# lighthouse-booster.net
KiCad netlist of a schematic drawn in EAGLE
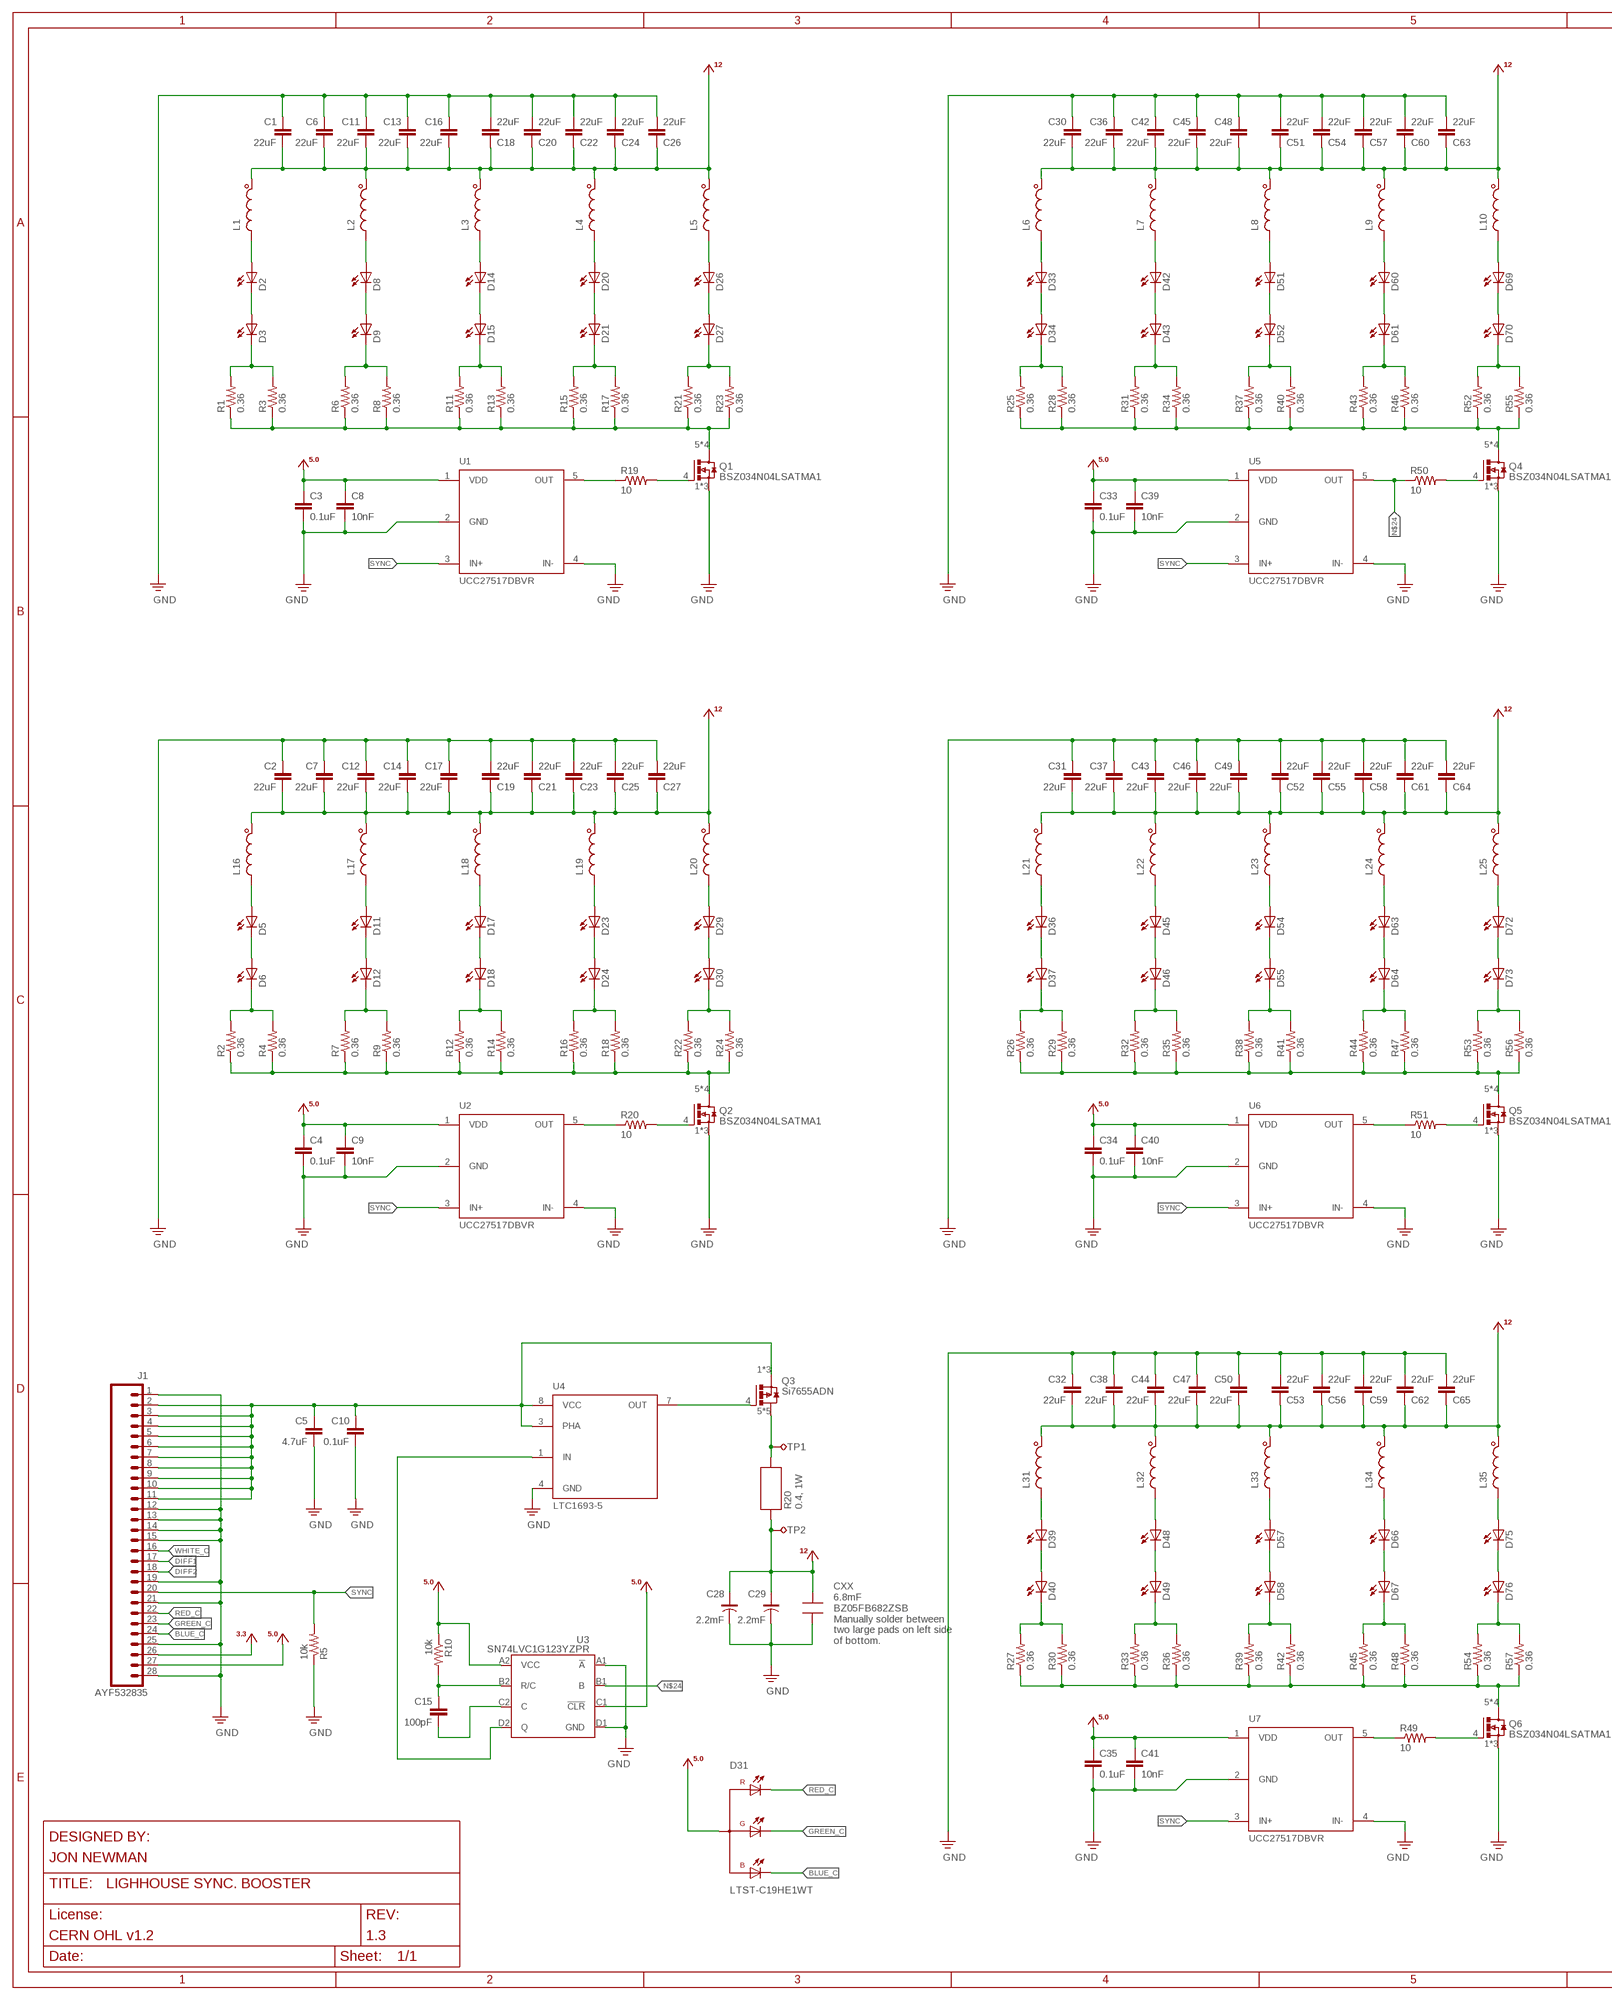
[diagram p0: schematic, sheet 1, part 1 of 2]
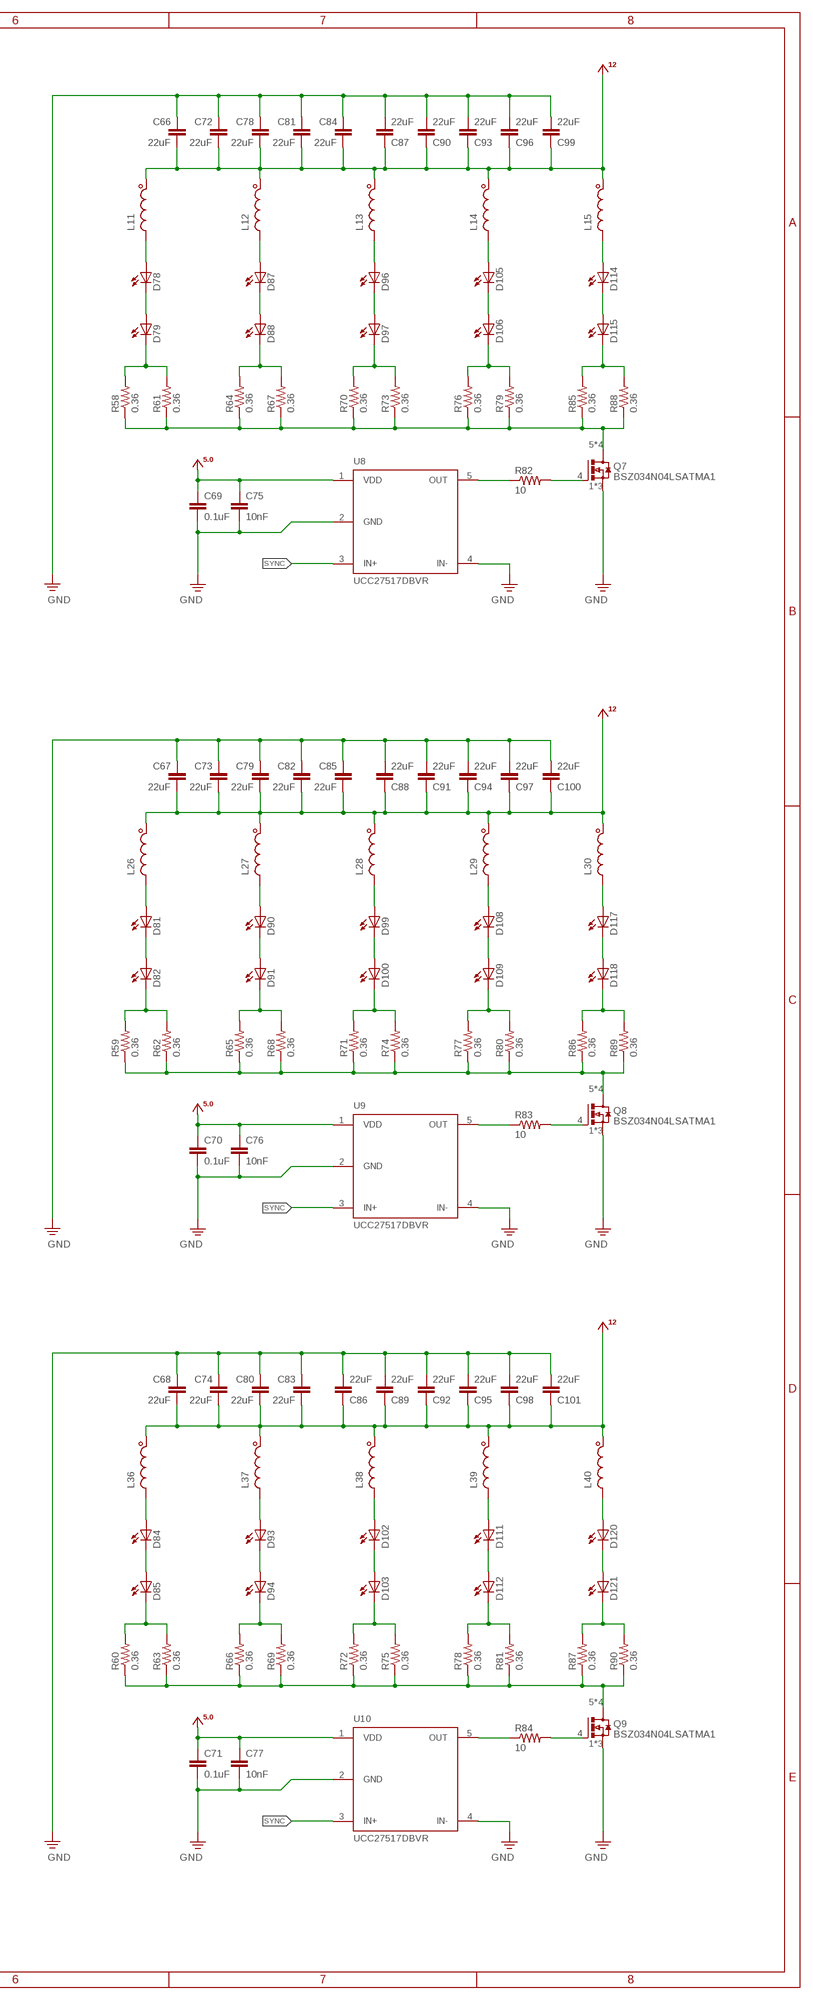
[diagram p1: schematic, sheet 1, part 2 of 2]

(export (version "E")
  (design (tool "Eeschema 10.0.6"))
  (components
    (comp (ref "C1")
      (value "22uF")
      (footprint "eagle-import:0805T")
      (libsource (lib "eagle-import") (part "C_0805T"))
    )
    (comp (ref "C2")
      (value "22uF")
      (footprint "eagle-import:0805T")
      (libsource (lib "eagle-import") (part "C_0805T"))
    )
    (comp (ref "C3")
      (value "0.1uF")
      (footprint "eagle-import:0402T")
      (libsource (lib "eagle-import") (part "C_0402T"))
    )
    (comp (ref "C4")
      (value "0.1uF")
      (footprint "eagle-import:0402T")
      (libsource (lib "eagle-import") (part "C_0402T"))
    )
    (comp (ref "C5")
      (value "4.7uF")
      (footprint "eagle-import:0603T")
      (libsource (lib "eagle-import") (part "C_0603T"))
    )
    (comp (ref "C6")
      (value "22uF")
      (footprint "eagle-import:0805T")
      (libsource (lib "eagle-import") (part "C_0805T"))
    )
    (comp (ref "C7")
      (value "22uF")
      (footprint "eagle-import:0805T")
      (libsource (lib "eagle-import") (part "C_0805T"))
    )
    (comp (ref "C8")
      (value "10nF")
      (footprint "eagle-import:0402T")
      (libsource (lib "eagle-import") (part "C_0402T"))
    )
    (comp (ref "C9")
      (value "10nF")
      (footprint "eagle-import:0402T")
      (libsource (lib "eagle-import") (part "C_0402T"))
    )
    (comp (ref "C10")
      (value "0.1uF")
      (footprint "eagle-import:0402T")
      (libsource (lib "eagle-import") (part "C_0402T"))
    )
    (comp (ref "C11")
      (value "22uF")
      (footprint "eagle-import:0805T")
      (libsource (lib "eagle-import") (part "C_0805T"))
    )
    (comp (ref "C12")
      (value "22uF")
      (footprint "eagle-import:0805T")
      (libsource (lib "eagle-import") (part "C_0805T"))
    )
    (comp (ref "C13")
      (value "22uF")
      (footprint "eagle-import:0805T")
      (libsource (lib "eagle-import") (part "C_0805T"))
    )
    (comp (ref "C14")
      (value "22uF")
      (footprint "eagle-import:0805T")
      (libsource (lib "eagle-import") (part "C_0805T"))
    )
    (comp (ref "C15")
      (value "100pF")
      (footprint "eagle-import:0402T")
      (libsource (lib "eagle-import") (part "C_0402T"))
    )
    (comp (ref "C16")
      (value "22uF")
      (footprint "eagle-import:0805T")
      (libsource (lib "eagle-import") (part "C_0805T"))
    )
    (comp (ref "C17")
      (value "22uF")
      (footprint "eagle-import:0805T")
      (libsource (lib "eagle-import") (part "C_0805T"))
    )
    (comp (ref "C18")
      (value "22uF")
      (footprint "eagle-import:0805T")
      (libsource (lib "eagle-import") (part "C_0805T"))
    )
    (comp (ref "C19")
      (value "22uF")
      (footprint "eagle-import:0805T")
      (libsource (lib "eagle-import") (part "C_0805T"))
    )
    (comp (ref "C20")
      (value "22uF")
      (footprint "eagle-import:0805T")
      (libsource (lib "eagle-import") (part "C_0805T"))
    )
    (comp (ref "C21")
      (value "22uF")
      (footprint "eagle-import:0805T")
      (libsource (lib "eagle-import") (part "C_0805T"))
    )
    (comp (ref "C22")
      (value "22uF")
      (footprint "eagle-import:0805T")
      (libsource (lib "eagle-import") (part "C_0805T"))
    )
    (comp (ref "C23")
      (value "22uF")
      (footprint "eagle-import:0805T")
      (libsource (lib "eagle-import") (part "C_0805T"))
    )
    (comp (ref "C24")
      (value "22uF")
      (footprint "eagle-import:0805T")
      (libsource (lib "eagle-import") (part "C_0805T"))
    )
    (comp (ref "C25")
      (value "22uF")
      (footprint "eagle-import:0805T")
      (libsource (lib "eagle-import") (part "C_0805T"))
    )
    (comp (ref "C26")
      (value "22uF")
      (footprint "eagle-import:0805T")
      (libsource (lib "eagle-import") (part "C_0805T"))
    )
    (comp (ref "C27")
      (value "22uF")
      (footprint "eagle-import:0805T")
      (libsource (lib "eagle-import") (part "C_0805T"))
    )
    (comp (ref "C28")
      (value "2.2mF")
      (footprint "eagle-import:C5MMA-SMD")
      (libsource (lib "eagle-import") (part "C-POL_C5MMA-SMD"))
    )
    (comp (ref "C29")
      (value "2.2mF")
      (footprint "eagle-import:C5MMA-SMD")
      (libsource (lib "eagle-import") (part "C-POL_C5MMA-SMD"))
    )
    (comp (ref "C30")
      (value "22uF")
      (footprint "eagle-import:0805T")
      (libsource (lib "eagle-import") (part "C_0805T"))
    )
    (comp (ref "C31")
      (value "22uF")
      (footprint "eagle-import:0805T")
      (libsource (lib "eagle-import") (part "C_0805T"))
    )
    (comp (ref "C32")
      (value "22uF")
      (footprint "eagle-import:0805T")
      (libsource (lib "eagle-import") (part "C_0805T"))
    )
    (comp (ref "C33")
      (value "0.1uF")
      (footprint "eagle-import:0402T")
      (libsource (lib "eagle-import") (part "C_0402T"))
    )
    (comp (ref "C34")
      (value "0.1uF")
      (footprint "eagle-import:0402T")
      (libsource (lib "eagle-import") (part "C_0402T"))
    )
    (comp (ref "C35")
      (value "0.1uF")
      (footprint "eagle-import:0402T")
      (libsource (lib "eagle-import") (part "C_0402T"))
    )
    (comp (ref "C36")
      (value "22uF")
      (footprint "eagle-import:0805T")
      (libsource (lib "eagle-import") (part "C_0805T"))
    )
    (comp (ref "C37")
      (value "22uF")
      (footprint "eagle-import:0805T")
      (libsource (lib "eagle-import") (part "C_0805T"))
    )
    (comp (ref "C38")
      (value "22uF")
      (footprint "eagle-import:0805T")
      (libsource (lib "eagle-import") (part "C_0805T"))
    )
    (comp (ref "C39")
      (value "10nF")
      (footprint "eagle-import:0402T")
      (libsource (lib "eagle-import") (part "C_0402T"))
    )
    (comp (ref "C40")
      (value "10nF")
      (footprint "eagle-import:0402T")
      (libsource (lib "eagle-import") (part "C_0402T"))
    )
    (comp (ref "C41")
      (value "10nF")
      (footprint "eagle-import:0402T")
      (libsource (lib "eagle-import") (part "C_0402T"))
    )
    (comp (ref "C42")
      (value "22uF")
      (footprint "eagle-import:0805T")
      (libsource (lib "eagle-import") (part "C_0805T"))
    )
    (comp (ref "C43")
      (value "22uF")
      (footprint "eagle-import:0805T")
      (libsource (lib "eagle-import") (part "C_0805T"))
    )
    (comp (ref "C44")
      (value "22uF")
      (footprint "eagle-import:0805T")
      (libsource (lib "eagle-import") (part "C_0805T"))
    )
    (comp (ref "C45")
      (value "22uF")
      (footprint "eagle-import:0805T")
      (libsource (lib "eagle-import") (part "C_0805T"))
    )
    (comp (ref "C46")
      (value "22uF")
      (footprint "eagle-import:0805T")
      (libsource (lib "eagle-import") (part "C_0805T"))
    )
    (comp (ref "C47")
      (value "22uF")
      (footprint "eagle-import:0805T")
      (libsource (lib "eagle-import") (part "C_0805T"))
    )
    (comp (ref "C48")
      (value "22uF")
      (footprint "eagle-import:0805T")
      (libsource (lib "eagle-import") (part "C_0805T"))
    )
    (comp (ref "C49")
      (value "22uF")
      (footprint "eagle-import:0805T")
      (libsource (lib "eagle-import") (part "C_0805T"))
    )
    (comp (ref "C50")
      (value "22uF")
      (footprint "eagle-import:0805T")
      (libsource (lib "eagle-import") (part "C_0805T"))
    )
    (comp (ref "C51")
      (value "22uF")
      (footprint "eagle-import:0805T")
      (libsource (lib "eagle-import") (part "C_0805T"))
    )
    (comp (ref "C52")
      (value "22uF")
      (footprint "eagle-import:0805T")
      (libsource (lib "eagle-import") (part "C_0805T"))
    )
    (comp (ref "C53")
      (value "22uF")
      (footprint "eagle-import:0805T")
      (libsource (lib "eagle-import") (part "C_0805T"))
    )
    (comp (ref "C54")
      (value "22uF")
      (footprint "eagle-import:0805T")
      (libsource (lib "eagle-import") (part "C_0805T"))
    )
    (comp (ref "C55")
      (value "22uF")
      (footprint "eagle-import:0805T")
      (libsource (lib "eagle-import") (part "C_0805T"))
    )
    (comp (ref "C56")
      (value "22uF")
      (footprint "eagle-import:0805T")
      (libsource (lib "eagle-import") (part "C_0805T"))
    )
    (comp (ref "C57")
      (value "22uF")
      (footprint "eagle-import:0805T")
      (libsource (lib "eagle-import") (part "C_0805T"))
    )
    (comp (ref "C58")
      (value "22uF")
      (footprint "eagle-import:0805T")
      (libsource (lib "eagle-import") (part "C_0805T"))
    )
    (comp (ref "C59")
      (value "22uF")
      (footprint "eagle-import:0805T")
      (libsource (lib "eagle-import") (part "C_0805T"))
    )
    (comp (ref "C60")
      (value "22uF")
      (footprint "eagle-import:0805T")
      (libsource (lib "eagle-import") (part "C_0805T"))
    )
    (comp (ref "C61")
      (value "22uF")
      (footprint "eagle-import:0805T")
      (libsource (lib "eagle-import") (part "C_0805T"))
    )
    (comp (ref "C62")
      (value "22uF")
      (footprint "eagle-import:0805T")
      (libsource (lib "eagle-import") (part "C_0805T"))
    )
    (comp (ref "C63")
      (value "22uF")
      (footprint "eagle-import:0805T")
      (libsource (lib "eagle-import") (part "C_0805T"))
    )
    (comp (ref "C64")
      (value "22uF")
      (footprint "eagle-import:0805T")
      (libsource (lib "eagle-import") (part "C_0805T"))
    )
    (comp (ref "C65")
      (value "22uF")
      (footprint "eagle-import:0805T")
      (libsource (lib "eagle-import") (part "C_0805T"))
    )
    (comp (ref "C66")
      (value "22uF")
      (footprint "eagle-import:0805T")
      (libsource (lib "eagle-import") (part "C_0805T"))
    )
    (comp (ref "C67")
      (value "22uF")
      (footprint "eagle-import:0805T")
      (libsource (lib "eagle-import") (part "C_0805T"))
    )
    (comp (ref "C68")
      (value "22uF")
      (footprint "eagle-import:0805T")
      (libsource (lib "eagle-import") (part "C_0805T"))
    )
    (comp (ref "C69")
      (value "0.1uF")
      (footprint "eagle-import:0402T")
      (libsource (lib "eagle-import") (part "C_0402T"))
    )
    (comp (ref "C70")
      (value "0.1uF")
      (footprint "eagle-import:0402T")
      (libsource (lib "eagle-import") (part "C_0402T"))
    )
    (comp (ref "C71")
      (value "0.1uF")
      (footprint "eagle-import:0402T")
      (libsource (lib "eagle-import") (part "C_0402T"))
    )
    (comp (ref "C72")
      (value "22uF")
      (footprint "eagle-import:0805T")
      (libsource (lib "eagle-import") (part "C_0805T"))
    )
    (comp (ref "C73")
      (value "22uF")
      (footprint "eagle-import:0805T")
      (libsource (lib "eagle-import") (part "C_0805T"))
    )
    (comp (ref "C74")
      (value "22uF")
      (footprint "eagle-import:0805T")
      (libsource (lib "eagle-import") (part "C_0805T"))
    )
    (comp (ref "C75")
      (value "10nF")
      (footprint "eagle-import:0402T")
      (libsource (lib "eagle-import") (part "C_0402T"))
    )
    (comp (ref "C76")
      (value "10nF")
      (footprint "eagle-import:0402T")
      (libsource (lib "eagle-import") (part "C_0402T"))
    )
    (comp (ref "C77")
      (value "10nF")
      (footprint "eagle-import:0402T")
      (libsource (lib "eagle-import") (part "C_0402T"))
    )
    (comp (ref "C78")
      (value "22uF")
      (footprint "eagle-import:0805T")
      (libsource (lib "eagle-import") (part "C_0805T"))
    )
    (comp (ref "C79")
      (value "22uF")
      (footprint "eagle-import:0805T")
      (libsource (lib "eagle-import") (part "C_0805T"))
    )
    (comp (ref "C80")
      (value "22uF")
      (footprint "eagle-import:0805T")
      (libsource (lib "eagle-import") (part "C_0805T"))
    )
    (comp (ref "C81")
      (value "22uF")
      (footprint "eagle-import:0805T")
      (libsource (lib "eagle-import") (part "C_0805T"))
    )
    (comp (ref "C82")
      (value "22uF")
      (footprint "eagle-import:0805T")
      (libsource (lib "eagle-import") (part "C_0805T"))
    )
    (comp (ref "C83")
      (value "22uF")
      (footprint "eagle-import:0805T")
      (libsource (lib "eagle-import") (part "C_0805T"))
    )
    (comp (ref "C84")
      (value "22uF")
      (footprint "eagle-import:0805T")
      (libsource (lib "eagle-import") (part "C_0805T"))
    )
    (comp (ref "C85")
      (value "22uF")
      (footprint "eagle-import:0805T")
      (libsource (lib "eagle-import") (part "C_0805T"))
    )
    (comp (ref "C86")
      (value "22uF")
      (footprint "eagle-import:0805T")
      (libsource (lib "eagle-import") (part "C_0805T"))
    )
    (comp (ref "C87")
      (value "22uF")
      (footprint "eagle-import:0805T")
      (libsource (lib "eagle-import") (part "C_0805T"))
    )
    (comp (ref "C88")
      (value "22uF")
      (footprint "eagle-import:0805T")
      (libsource (lib "eagle-import") (part "C_0805T"))
    )
    (comp (ref "C89")
      (value "22uF")
      (footprint "eagle-import:0805T")
      (libsource (lib "eagle-import") (part "C_0805T"))
    )
    (comp (ref "C90")
      (value "22uF")
      (footprint "eagle-import:0805T")
      (libsource (lib "eagle-import") (part "C_0805T"))
    )
    (comp (ref "C91")
      (value "22uF")
      (footprint "eagle-import:0805T")
      (libsource (lib "eagle-import") (part "C_0805T"))
    )
    (comp (ref "C92")
      (value "22uF")
      (footprint "eagle-import:0805T")
      (libsource (lib "eagle-import") (part "C_0805T"))
    )
    (comp (ref "C93")
      (value "22uF")
      (footprint "eagle-import:0805T")
      (libsource (lib "eagle-import") (part "C_0805T"))
    )
    (comp (ref "C94")
      (value "22uF")
      (footprint "eagle-import:0805T")
      (libsource (lib "eagle-import") (part "C_0805T"))
    )
    (comp (ref "C95")
      (value "22uF")
      (footprint "eagle-import:0805T")
      (libsource (lib "eagle-import") (part "C_0805T"))
    )
    (comp (ref "C96")
      (value "22uF")
      (footprint "eagle-import:0805T")
      (libsource (lib "eagle-import") (part "C_0805T"))
    )
    (comp (ref "C97")
      (value "22uF")
      (footprint "eagle-import:0805T")
      (libsource (lib "eagle-import") (part "C_0805T"))
    )
    (comp (ref "C98")
      (value "22uF")
      (footprint "eagle-import:0805T")
      (libsource (lib "eagle-import") (part "C_0805T"))
    )
    (comp (ref "C99")
      (value "22uF")
      (footprint "eagle-import:0805T")
      (libsource (lib "eagle-import") (part "C_0805T"))
    )
    (comp (ref "C100")
      (value "22uF")
      (footprint "eagle-import:0805T")
      (libsource (lib "eagle-import") (part "C_0805T"))
    )
    (comp (ref "C101")
      (value "22uF")
      (footprint "eagle-import:0805T")
      (libsource (lib "eagle-import") (part "C_0805T"))
    )
    (comp (ref "D2")
      (value "LED_LUXEON-3.7MM")
      (footprint "eagle-import:LUXEON-3.7MM")
      (libsource (lib "eagle-import") (part "LED_LUXEON-3.7MM"))
    )
    (comp (ref "D3")
      (value "LED_LUXEON-3.7MM")
      (footprint "eagle-import:LUXEON-3.7MM")
      (libsource (lib "eagle-import") (part "LED_LUXEON-3.7MM"))
    )
    (comp (ref "D5")
      (value "LED_LUXEON-3.7MM")
      (footprint "eagle-import:LUXEON-3.7MM")
      (libsource (lib "eagle-import") (part "LED_LUXEON-3.7MM"))
    )
    (comp (ref "D6")
      (value "LED_LUXEON-3.7MM")
      (footprint "eagle-import:LUXEON-3.7MM")
      (libsource (lib "eagle-import") (part "LED_LUXEON-3.7MM"))
    )
    (comp (ref "D8")
      (value "LED_LUXEON-3.7MM")
      (footprint "eagle-import:LUXEON-3.7MM")
      (libsource (lib "eagle-import") (part "LED_LUXEON-3.7MM"))
    )
    (comp (ref "D9")
      (value "LED_LUXEON-3.7MM")
      (footprint "eagle-import:LUXEON-3.7MM")
      (libsource (lib "eagle-import") (part "LED_LUXEON-3.7MM"))
    )
    (comp (ref "D11")
      (value "LED_LUXEON-3.7MM")
      (footprint "eagle-import:LUXEON-3.7MM")
      (libsource (lib "eagle-import") (part "LED_LUXEON-3.7MM"))
    )
    (comp (ref "D12")
      (value "LED_LUXEON-3.7MM")
      (footprint "eagle-import:LUXEON-3.7MM")
      (libsource (lib "eagle-import") (part "LED_LUXEON-3.7MM"))
    )
    (comp (ref "D14")
      (value "LED_LUXEON-3.7MM")
      (footprint "eagle-import:LUXEON-3.7MM")
      (libsource (lib "eagle-import") (part "LED_LUXEON-3.7MM"))
    )
    (comp (ref "D15")
      (value "LED_LUXEON-3.7MM")
      (footprint "eagle-import:LUXEON-3.7MM")
      (libsource (lib "eagle-import") (part "LED_LUXEON-3.7MM"))
    )
    (comp (ref "D17")
      (value "LED_LUXEON-3.7MM")
      (footprint "eagle-import:LUXEON-3.7MM")
      (libsource (lib "eagle-import") (part "LED_LUXEON-3.7MM"))
    )
    (comp (ref "D18")
      (value "LED_LUXEON-3.7MM")
      (footprint "eagle-import:LUXEON-3.7MM")
      (libsource (lib "eagle-import") (part "LED_LUXEON-3.7MM"))
    )
    (comp (ref "D20")
      (value "LED_LUXEON-3.7MM")
      (footprint "eagle-import:LUXEON-3.7MM")
      (libsource (lib "eagle-import") (part "LED_LUXEON-3.7MM"))
    )
    (comp (ref "D21")
      (value "LED_LUXEON-3.7MM")
      (footprint "eagle-import:LUXEON-3.7MM")
      (libsource (lib "eagle-import") (part "LED_LUXEON-3.7MM"))
    )
    (comp (ref "D23")
      (value "LED_LUXEON-3.7MM")
      (footprint "eagle-import:LUXEON-3.7MM")
      (libsource (lib "eagle-import") (part "LED_LUXEON-3.7MM"))
    )
    (comp (ref "D24")
      (value "LED_LUXEON-3.7MM")
      (footprint "eagle-import:LUXEON-3.7MM")
      (libsource (lib "eagle-import") (part "LED_LUXEON-3.7MM"))
    )
    (comp (ref "D26")
      (value "LED_LUXEON-3.7MM")
      (footprint "eagle-import:LUXEON-3.7MM")
      (libsource (lib "eagle-import") (part "LED_LUXEON-3.7MM"))
    )
    (comp (ref "D27")
      (value "LED_LUXEON-3.7MM")
      (footprint "eagle-import:LUXEON-3.7MM")
      (libsource (lib "eagle-import") (part "LED_LUXEON-3.7MM"))
    )
    (comp (ref "D29")
      (value "LED_LUXEON-3.7MM")
      (footprint "eagle-import:LUXEON-3.7MM")
      (libsource (lib "eagle-import") (part "LED_LUXEON-3.7MM"))
    )
    (comp (ref "D30")
      (value "LED_LUXEON-3.7MM")
      (footprint "eagle-import:LUXEON-3.7MM")
      (libsource (lib "eagle-import") (part "LED_LUXEON-3.7MM"))
    )
    (comp (ref "D31")
      (value "LTST-C19HE1WT")
      (footprint "eagle-import:LTST-C19HE1WT")
      (libsource (lib "eagle-import") (part "LED-RGB_LTST"))
    )
    (comp (ref "D33")
      (value "LED_LUXEON-3.7MM")
      (footprint "eagle-import:LUXEON-3.7MM")
      (libsource (lib "eagle-import") (part "LED_LUXEON-3.7MM"))
    )
    (comp (ref "D34")
      (value "LED_LUXEON-3.7MM")
      (footprint "eagle-import:LUXEON-3.7MM")
      (libsource (lib "eagle-import") (part "LED_LUXEON-3.7MM"))
    )
    (comp (ref "D36")
      (value "LED_LUXEON-3.7MM")
      (footprint "eagle-import:LUXEON-3.7MM")
      (libsource (lib "eagle-import") (part "LED_LUXEON-3.7MM"))
    )
    (comp (ref "D37")
      (value "LED_LUXEON-3.7MM")
      (footprint "eagle-import:LUXEON-3.7MM")
      (libsource (lib "eagle-import") (part "LED_LUXEON-3.7MM"))
    )
    (comp (ref "D39")
      (value "LED_LUXEON-3.7MM")
      (footprint "eagle-import:LUXEON-3.7MM")
      (libsource (lib "eagle-import") (part "LED_LUXEON-3.7MM"))
    )
    (comp (ref "D40")
      (value "LED_LUXEON-3.7MM")
      (footprint "eagle-import:LUXEON-3.7MM")
      (libsource (lib "eagle-import") (part "LED_LUXEON-3.7MM"))
    )
    (comp (ref "D42")
      (value "LED_LUXEON-3.7MM")
      (footprint "eagle-import:LUXEON-3.7MM")
      (libsource (lib "eagle-import") (part "LED_LUXEON-3.7MM"))
    )
    (comp (ref "D43")
      (value "LED_LUXEON-3.7MM")
      (footprint "eagle-import:LUXEON-3.7MM")
      (libsource (lib "eagle-import") (part "LED_LUXEON-3.7MM"))
    )
    (comp (ref "D45")
      (value "LED_LUXEON-3.7MM")
      (footprint "eagle-import:LUXEON-3.7MM")
      (libsource (lib "eagle-import") (part "LED_LUXEON-3.7MM"))
    )
    (comp (ref "D46")
      (value "LED_LUXEON-3.7MM")
      (footprint "eagle-import:LUXEON-3.7MM")
      (libsource (lib "eagle-import") (part "LED_LUXEON-3.7MM"))
    )
    (comp (ref "D48")
      (value "LED_LUXEON-3.7MM")
      (footprint "eagle-import:LUXEON-3.7MM")
      (libsource (lib "eagle-import") (part "LED_LUXEON-3.7MM"))
    )
    (comp (ref "D49")
      (value "LED_LUXEON-3.7MM")
      (footprint "eagle-import:LUXEON-3.7MM")
      (libsource (lib "eagle-import") (part "LED_LUXEON-3.7MM"))
    )
    (comp (ref "D51")
      (value "LED_LUXEON-3.7MM")
      (footprint "eagle-import:LUXEON-3.7MM")
      (libsource (lib "eagle-import") (part "LED_LUXEON-3.7MM"))
    )
    (comp (ref "D52")
      (value "LED_LUXEON-3.7MM")
      (footprint "eagle-import:LUXEON-3.7MM")
      (libsource (lib "eagle-import") (part "LED_LUXEON-3.7MM"))
    )
    (comp (ref "D54")
      (value "LED_LUXEON-3.7MM")
      (footprint "eagle-import:LUXEON-3.7MM")
      (libsource (lib "eagle-import") (part "LED_LUXEON-3.7MM"))
    )
    (comp (ref "D55")
      (value "LED_LUXEON-3.7MM")
      (footprint "eagle-import:LUXEON-3.7MM")
      (libsource (lib "eagle-import") (part "LED_LUXEON-3.7MM"))
    )
    (comp (ref "D57")
      (value "LED_LUXEON-3.7MM")
      (footprint "eagle-import:LUXEON-3.7MM")
      (libsource (lib "eagle-import") (part "LED_LUXEON-3.7MM"))
    )
    (comp (ref "D58")
      (value "LED_LUXEON-3.7MM")
      (footprint "eagle-import:LUXEON-3.7MM")
      (libsource (lib "eagle-import") (part "LED_LUXEON-3.7MM"))
    )
    (comp (ref "D60")
      (value "LED_LUXEON-3.7MM")
      (footprint "eagle-import:LUXEON-3.7MM")
      (libsource (lib "eagle-import") (part "LED_LUXEON-3.7MM"))
    )
    (comp (ref "D61")
      (value "LED_LUXEON-3.7MM")
      (footprint "eagle-import:LUXEON-3.7MM")
      (libsource (lib "eagle-import") (part "LED_LUXEON-3.7MM"))
    )
    (comp (ref "D63")
      (value "LED_LUXEON-3.7MM")
      (footprint "eagle-import:LUXEON-3.7MM")
      (libsource (lib "eagle-import") (part "LED_LUXEON-3.7MM"))
    )
    (comp (ref "D64")
      (value "LED_LUXEON-3.7MM")
      (footprint "eagle-import:LUXEON-3.7MM")
      (libsource (lib "eagle-import") (part "LED_LUXEON-3.7MM"))
    )
    (comp (ref "D66")
      (value "LED_LUXEON-3.7MM")
      (footprint "eagle-import:LUXEON-3.7MM")
      (libsource (lib "eagle-import") (part "LED_LUXEON-3.7MM"))
    )
    (comp (ref "D67")
      (value "LED_LUXEON-3.7MM")
      (footprint "eagle-import:LUXEON-3.7MM")
      (libsource (lib "eagle-import") (part "LED_LUXEON-3.7MM"))
    )
    (comp (ref "D69")
      (value "LED_LUXEON-3.7MM")
      (footprint "eagle-import:LUXEON-3.7MM")
      (libsource (lib "eagle-import") (part "LED_LUXEON-3.7MM"))
    )
    (comp (ref "D70")
      (value "LED_LUXEON-3.7MM")
      (footprint "eagle-import:LUXEON-3.7MM")
      (libsource (lib "eagle-import") (part "LED_LUXEON-3.7MM"))
    )
    (comp (ref "D72")
      (value "LED_LUXEON-3.7MM")
      (footprint "eagle-import:LUXEON-3.7MM")
      (libsource (lib "eagle-import") (part "LED_LUXEON-3.7MM"))
    )
    (comp (ref "D73")
      (value "LED_LUXEON-3.7MM")
      (footprint "eagle-import:LUXEON-3.7MM")
      (libsource (lib "eagle-import") (part "LED_LUXEON-3.7MM"))
    )
    (comp (ref "D75")
      (value "LED_LUXEON-3.7MM")
      (footprint "eagle-import:LUXEON-3.7MM")
      (libsource (lib "eagle-import") (part "LED_LUXEON-3.7MM"))
    )
    (comp (ref "D76")
      (value "LED_LUXEON-3.7MM")
      (footprint "eagle-import:LUXEON-3.7MM")
      (libsource (lib "eagle-import") (part "LED_LUXEON-3.7MM"))
    )
    (comp (ref "D78")
      (value "LED_LUXEON-3.7MM")
      (footprint "eagle-import:LUXEON-3.7MM")
      (libsource (lib "eagle-import") (part "LED_LUXEON-3.7MM"))
    )
    (comp (ref "D79")
      (value "LED_LUXEON-3.7MM")
      (footprint "eagle-import:LUXEON-3.7MM")
      (libsource (lib "eagle-import") (part "LED_LUXEON-3.7MM"))
    )
    (comp (ref "D81")
      (value "LED_LUXEON-3.7MM")
      (footprint "eagle-import:LUXEON-3.7MM")
      (libsource (lib "eagle-import") (part "LED_LUXEON-3.7MM"))
    )
    (comp (ref "D82")
      (value "LED_LUXEON-3.7MM")
      (footprint "eagle-import:LUXEON-3.7MM")
      (libsource (lib "eagle-import") (part "LED_LUXEON-3.7MM"))
    )
    (comp (ref "D84")
      (value "LED_LUXEON-3.7MM")
      (footprint "eagle-import:LUXEON-3.7MM")
      (libsource (lib "eagle-import") (part "LED_LUXEON-3.7MM"))
    )
    (comp (ref "D85")
      (value "LED_LUXEON-3.7MM")
      (footprint "eagle-import:LUXEON-3.7MM")
      (libsource (lib "eagle-import") (part "LED_LUXEON-3.7MM"))
    )
    (comp (ref "D87")
      (value "LED_LUXEON-3.7MM")
      (footprint "eagle-import:LUXEON-3.7MM")
      (libsource (lib "eagle-import") (part "LED_LUXEON-3.7MM"))
    )
    (comp (ref "D88")
      (value "LED_LUXEON-3.7MM")
      (footprint "eagle-import:LUXEON-3.7MM")
      (libsource (lib "eagle-import") (part "LED_LUXEON-3.7MM"))
    )
    (comp (ref "D90")
      (value "LED_LUXEON-3.7MM")
      (footprint "eagle-import:LUXEON-3.7MM")
      (libsource (lib "eagle-import") (part "LED_LUXEON-3.7MM"))
    )
    (comp (ref "D91")
      (value "LED_LUXEON-3.7MM")
      (footprint "eagle-import:LUXEON-3.7MM")
      (libsource (lib "eagle-import") (part "LED_LUXEON-3.7MM"))
    )
    (comp (ref "D93")
      (value "LED_LUXEON-3.7MM")
      (footprint "eagle-import:LUXEON-3.7MM")
      (libsource (lib "eagle-import") (part "LED_LUXEON-3.7MM"))
    )
    (comp (ref "D94")
      (value "LED_LUXEON-3.7MM")
      (footprint "eagle-import:LUXEON-3.7MM")
      (libsource (lib "eagle-import") (part "LED_LUXEON-3.7MM"))
    )
    (comp (ref "D96")
      (value "LED_LUXEON-3.7MM")
      (footprint "eagle-import:LUXEON-3.7MM")
      (libsource (lib "eagle-import") (part "LED_LUXEON-3.7MM"))
    )
    (comp (ref "D97")
      (value "LED_LUXEON-3.7MM")
      (footprint "eagle-import:LUXEON-3.7MM")
      (libsource (lib "eagle-import") (part "LED_LUXEON-3.7MM"))
    )
    (comp (ref "D99")
      (value "LED_LUXEON-3.7MM")
      (footprint "eagle-import:LUXEON-3.7MM")
      (libsource (lib "eagle-import") (part "LED_LUXEON-3.7MM"))
    )
    (comp (ref "D100")
      (value "LED_LUXEON-3.7MM")
      (footprint "eagle-import:LUXEON-3.7MM")
      (libsource (lib "eagle-import") (part "LED_LUXEON-3.7MM"))
    )
    (comp (ref "D102")
      (value "LED_LUXEON-3.7MM")
      (footprint "eagle-import:LUXEON-3.7MM")
      (libsource (lib "eagle-import") (part "LED_LUXEON-3.7MM"))
    )
    (comp (ref "D103")
      (value "LED_LUXEON-3.7MM")
      (footprint "eagle-import:LUXEON-3.7MM")
      (libsource (lib "eagle-import") (part "LED_LUXEON-3.7MM"))
    )
    (comp (ref "D105")
      (value "LED_LUXEON-3.7MM")
      (footprint "eagle-import:LUXEON-3.7MM")
      (libsource (lib "eagle-import") (part "LED_LUXEON-3.7MM"))
    )
    (comp (ref "D106")
      (value "LED_LUXEON-3.7MM")
      (footprint "eagle-import:LUXEON-3.7MM")
      (libsource (lib "eagle-import") (part "LED_LUXEON-3.7MM"))
    )
    (comp (ref "D108")
      (value "LED_LUXEON-3.7MM")
      (footprint "eagle-import:LUXEON-3.7MM")
      (libsource (lib "eagle-import") (part "LED_LUXEON-3.7MM"))
    )
    (comp (ref "D109")
      (value "LED_LUXEON-3.7MM")
      (footprint "eagle-import:LUXEON-3.7MM")
      (libsource (lib "eagle-import") (part "LED_LUXEON-3.7MM"))
    )
    (comp (ref "D111")
      (value "LED_LUXEON-3.7MM")
      (footprint "eagle-import:LUXEON-3.7MM")
      (libsource (lib "eagle-import") (part "LED_LUXEON-3.7MM"))
    )
    (comp (ref "D112")
      (value "LED_LUXEON-3.7MM")
      (footprint "eagle-import:LUXEON-3.7MM")
      (libsource (lib "eagle-import") (part "LED_LUXEON-3.7MM"))
    )
    (comp (ref "D114")
      (value "LED_LUXEON-3.7MM")
      (footprint "eagle-import:LUXEON-3.7MM")
      (libsource (lib "eagle-import") (part "LED_LUXEON-3.7MM"))
    )
    (comp (ref "D115")
      (value "LED_LUXEON-3.7MM")
      (footprint "eagle-import:LUXEON-3.7MM")
      (libsource (lib "eagle-import") (part "LED_LUXEON-3.7MM"))
    )
    (comp (ref "D117")
      (value "LED_LUXEON-3.7MM")
      (footprint "eagle-import:LUXEON-3.7MM")
      (libsource (lib "eagle-import") (part "LED_LUXEON-3.7MM"))
    )
    (comp (ref "D118")
      (value "LED_LUXEON-3.7MM")
      (footprint "eagle-import:LUXEON-3.7MM")
      (libsource (lib "eagle-import") (part "LED_LUXEON-3.7MM"))
    )
    (comp (ref "D120")
      (value "LED_LUXEON-3.7MM")
      (footprint "eagle-import:LUXEON-3.7MM")
      (libsource (lib "eagle-import") (part "LED_LUXEON-3.7MM"))
    )
    (comp (ref "D121")
      (value "LED_LUXEON-3.7MM")
      (footprint "eagle-import:LUXEON-3.7MM")
      (libsource (lib "eagle-import") (part "LED_LUXEON-3.7MM"))
    )
    (comp (ref "J1")
      (value "AYF532835")
      (footprint "eagle-import:Y5B_Y5BW-28")
      (libsource (lib "eagle-import") (part "PINHD-1X28_Y5B"))
    )
    (comp (ref "L1")
      (value "L_0805T")
      (footprint "eagle-import:0805T")
      (libsource (lib "eagle-import") (part "L_0805T"))
    )
    (comp (ref "L2")
      (value "L_0805T")
      (footprint "eagle-import:0805T")
      (libsource (lib "eagle-import") (part "L_0805T"))
    )
    (comp (ref "L3")
      (value "L_0805T")
      (footprint "eagle-import:0805T")
      (libsource (lib "eagle-import") (part "L_0805T"))
    )
    (comp (ref "L4")
      (value "L_0805T")
      (footprint "eagle-import:0805T")
      (libsource (lib "eagle-import") (part "L_0805T"))
    )
    (comp (ref "L5")
      (value "L_0805T")
      (footprint "eagle-import:0805T")
      (libsource (lib "eagle-import") (part "L_0805T"))
    )
    (comp (ref "L6")
      (value "L_0805T")
      (footprint "eagle-import:0805T")
      (libsource (lib "eagle-import") (part "L_0805T"))
    )
    (comp (ref "L7")
      (value "L_0805T")
      (footprint "eagle-import:0805T")
      (libsource (lib "eagle-import") (part "L_0805T"))
    )
    (comp (ref "L8")
      (value "L_0805T")
      (footprint "eagle-import:0805T")
      (libsource (lib "eagle-import") (part "L_0805T"))
    )
    (comp (ref "L9")
      (value "L_0805T")
      (footprint "eagle-import:0805T")
      (libsource (lib "eagle-import") (part "L_0805T"))
    )
    (comp (ref "L10")
      (value "L_0805T")
      (footprint "eagle-import:0805T")
      (libsource (lib "eagle-import") (part "L_0805T"))
    )
    (comp (ref "L11")
      (value "L_0805T")
      (footprint "eagle-import:0805T")
      (libsource (lib "eagle-import") (part "L_0805T"))
    )
    (comp (ref "L12")
      (value "L_0805T")
      (footprint "eagle-import:0805T")
      (libsource (lib "eagle-import") (part "L_0805T"))
    )
    (comp (ref "L13")
      (value "L_0805T")
      (footprint "eagle-import:0805T")
      (libsource (lib "eagle-import") (part "L_0805T"))
    )
    (comp (ref "L14")
      (value "L_0805T")
      (footprint "eagle-import:0805T")
      (libsource (lib "eagle-import") (part "L_0805T"))
    )
    (comp (ref "L15")
      (value "L_0805T")
      (footprint "eagle-import:0805T")
      (libsource (lib "eagle-import") (part "L_0805T"))
    )
    (comp (ref "L16")
      (value "L_0805T")
      (footprint "eagle-import:0805T")
      (libsource (lib "eagle-import") (part "L_0805T"))
    )
    (comp (ref "L17")
      (value "L_0805T")
      (footprint "eagle-import:0805T")
      (libsource (lib "eagle-import") (part "L_0805T"))
    )
    (comp (ref "L18")
      (value "L_0805T")
      (footprint "eagle-import:0805T")
      (libsource (lib "eagle-import") (part "L_0805T"))
    )
    (comp (ref "L19")
      (value "L_0805T")
      (footprint "eagle-import:0805T")
      (libsource (lib "eagle-import") (part "L_0805T"))
    )
    (comp (ref "L20")
      (value "L_0805T")
      (footprint "eagle-import:0805T")
      (libsource (lib "eagle-import") (part "L_0805T"))
    )
    (comp (ref "L21")
      (value "L_0805T")
      (footprint "eagle-import:0805T")
      (libsource (lib "eagle-import") (part "L_0805T"))
    )
    (comp (ref "L22")
      (value "L_0805T")
      (footprint "eagle-import:0805T")
      (libsource (lib "eagle-import") (part "L_0805T"))
    )
    (comp (ref "L23")
      (value "L_0805T")
      (footprint "eagle-import:0805T")
      (libsource (lib "eagle-import") (part "L_0805T"))
    )
    (comp (ref "L24")
      (value "L_0805T")
      (footprint "eagle-import:0805T")
      (libsource (lib "eagle-import") (part "L_0805T"))
    )
    (comp (ref "L25")
      (value "L_0805T")
      (footprint "eagle-import:0805T")
      (libsource (lib "eagle-import") (part "L_0805T"))
    )
    (comp (ref "L26")
      (value "L_0805T")
      (footprint "eagle-import:0805T")
      (libsource (lib "eagle-import") (part "L_0805T"))
    )
    (comp (ref "L27")
      (value "L_0805T")
      (footprint "eagle-import:0805T")
      (libsource (lib "eagle-import") (part "L_0805T"))
    )
    (comp (ref "L28")
      (value "L_0805T")
      (footprint "eagle-import:0805T")
      (libsource (lib "eagle-import") (part "L_0805T"))
    )
    (comp (ref "L29")
      (value "L_0805T")
      (footprint "eagle-import:0805T")
      (libsource (lib "eagle-import") (part "L_0805T"))
    )
    (comp (ref "L30")
      (value "L_0805T")
      (footprint "eagle-import:0805T")
      (libsource (lib "eagle-import") (part "L_0805T"))
    )
    (comp (ref "L31")
      (value "L_0805T")
      (footprint "eagle-import:0805T")
      (libsource (lib "eagle-import") (part "L_0805T"))
    )
    (comp (ref "L32")
      (value "L_0805T")
      (footprint "eagle-import:0805T")
      (libsource (lib "eagle-import") (part "L_0805T"))
    )
    (comp (ref "L33")
      (value "L_0805T")
      (footprint "eagle-import:0805T")
      (libsource (lib "eagle-import") (part "L_0805T"))
    )
    (comp (ref "L34")
      (value "L_0805T")
      (footprint "eagle-import:0805T")
      (libsource (lib "eagle-import") (part "L_0805T"))
    )
    (comp (ref "L35")
      (value "L_0805T")
      (footprint "eagle-import:0805T")
      (libsource (lib "eagle-import") (part "L_0805T"))
    )
    (comp (ref "L36")
      (value "L_0805T")
      (footprint "eagle-import:0805T")
      (libsource (lib "eagle-import") (part "L_0805T"))
    )
    (comp (ref "L37")
      (value "L_0805T")
      (footprint "eagle-import:0805T")
      (libsource (lib "eagle-import") (part "L_0805T"))
    )
    (comp (ref "L38")
      (value "L_0805T")
      (footprint "eagle-import:0805T")
      (libsource (lib "eagle-import") (part "L_0805T"))
    )
    (comp (ref "L39")
      (value "L_0805T")
      (footprint "eagle-import:0805T")
      (libsource (lib "eagle-import") (part "L_0805T"))
    )
    (comp (ref "L40")
      (value "L_0805T")
      (footprint "eagle-import:0805T")
      (libsource (lib "eagle-import") (part "L_0805T"))
    )
    (comp (ref "Q1")
      (value "BSZ034N04LSATMA1")
      (footprint "eagle-import:PG-TSDSON-8")
      (libsource (lib "eagle-import") (part "N-MOSFET_TSDSON-8"))
    )
    (comp (ref "Q2")
      (value "BSZ034N04LSATMA1")
      (footprint "eagle-import:PG-TSDSON-8")
      (libsource (lib "eagle-import") (part "N-MOSFET_TSDSON-8"))
    )
    (comp (ref "Q3")
      (value "Si7655ADN")
      (footprint "eagle-import:POWERPACK-1212-8")
      (libsource (lib "eagle-import") (part "P-MOSFET_POWERPACK-1212-8"))
    )
    (comp (ref "Q4")
      (value "BSZ034N04LSATMA1")
      (footprint "eagle-import:PG-TSDSON-8")
      (libsource (lib "eagle-import") (part "N-MOSFET_TSDSON-8"))
    )
    (comp (ref "Q5")
      (value "BSZ034N04LSATMA1")
      (footprint "eagle-import:PG-TSDSON-8")
      (libsource (lib "eagle-import") (part "N-MOSFET_TSDSON-8"))
    )
    (comp (ref "Q6")
      (value "BSZ034N04LSATMA1")
      (footprint "eagle-import:PG-TSDSON-8")
      (libsource (lib "eagle-import") (part "N-MOSFET_TSDSON-8"))
    )
    (comp (ref "Q7")
      (value "BSZ034N04LSATMA1")
      (footprint "eagle-import:PG-TSDSON-8")
      (libsource (lib "eagle-import") (part "N-MOSFET_TSDSON-8"))
    )
    (comp (ref "Q8")
      (value "BSZ034N04LSATMA1")
      (footprint "eagle-import:PG-TSDSON-8")
      (libsource (lib "eagle-import") (part "N-MOSFET_TSDSON-8"))
    )
    (comp (ref "Q9")
      (value "BSZ034N04LSATMA1")
      (footprint "eagle-import:PG-TSDSON-8")
      (libsource (lib "eagle-import") (part "N-MOSFET_TSDSON-8"))
    )
    (comp (ref "R1")
      (value "0.36")
      (footprint "eagle-import:0805T")
      (libsource (lib "eagle-import") (part "R_0805T"))
    )
    (comp (ref "R2")
      (value "0.36")
      (footprint "eagle-import:0805T")
      (libsource (lib "eagle-import") (part "R_0805T"))
    )
    (comp (ref "R3")
      (value "0.36")
      (footprint "eagle-import:0805T")
      (libsource (lib "eagle-import") (part "R_0805T"))
    )
    (comp (ref "R4")
      (value "0.36")
      (footprint "eagle-import:0805T")
      (libsource (lib "eagle-import") (part "R_0805T"))
    )
    (comp (ref "R5")
      (value "10k")
      (footprint "eagle-import:0402T")
      (libsource (lib "eagle-import") (part "R_0402T"))
    )
    (comp (ref "R6")
      (value "0.36")
      (footprint "eagle-import:0805T")
      (libsource (lib "eagle-import") (part "R_0805T"))
    )
    (comp (ref "R7")
      (value "0.36")
      (footprint "eagle-import:0805T")
      (libsource (lib "eagle-import") (part "R_0805T"))
    )
    (comp (ref "R8")
      (value "0.36")
      (footprint "eagle-import:0805T")
      (libsource (lib "eagle-import") (part "R_0805T"))
    )
    (comp (ref "R9")
      (value "0.36")
      (footprint "eagle-import:0805T")
      (libsource (lib "eagle-import") (part "R_0805T"))
    )
    (comp (ref "R10")
      (value "10k")
      (footprint "eagle-import:0402T")
      (libsource (lib "eagle-import") (part "R_0402T"))
    )
    (comp (ref "R11")
      (value "0.36")
      (footprint "eagle-import:0805T")
      (libsource (lib "eagle-import") (part "R_0805T"))
    )
    (comp (ref "R12")
      (value "0.36")
      (footprint "eagle-import:0805T")
      (libsource (lib "eagle-import") (part "R_0805T"))
    )
    (comp (ref "R13")
      (value "0.36")
      (footprint "eagle-import:0805T")
      (libsource (lib "eagle-import") (part "R_0805T"))
    )
    (comp (ref "R14")
      (value "0.36")
      (footprint "eagle-import:0805T")
      (libsource (lib "eagle-import") (part "R_0805T"))
    )
    (comp (ref "R15")
      (value "0.36")
      (footprint "eagle-import:0805T")
      (libsource (lib "eagle-import") (part "R_0805T"))
    )
    (comp (ref "R16")
      (value "0.36")
      (footprint "eagle-import:0805T")
      (libsource (lib "eagle-import") (part "R_0805T"))
    )
    (comp (ref "R17")
      (value "0.36")
      (footprint "eagle-import:0805T")
      (libsource (lib "eagle-import") (part "R_0805T"))
    )
    (comp (ref "R18")
      (value "0.36")
      (footprint "eagle-import:0805T")
      (libsource (lib "eagle-import") (part "R_0805T"))
    )
    (comp (ref "R19")
      (value "10")
      (footprint "eagle-import:0402T")
      (libsource (lib "eagle-import") (part "R_0402T"))
    )
    (comp (ref "R20")
      (value "10")
      (footprint "eagle-import:0402T")
      (libsource (lib "eagle-import") (part "R_0402T"))
    )
    (comp (ref "R21")
      (value "0.36")
      (footprint "eagle-import:0805T")
      (libsource (lib "eagle-import") (part "R_0805T"))
    )
    (comp (ref "R22")
      (value "0.36")
      (footprint "eagle-import:0805T")
      (libsource (lib "eagle-import") (part "R_0805T"))
    )
    (comp (ref "R23")
      (value "0.36")
      (footprint "eagle-import:0805T")
      (libsource (lib "eagle-import") (part "R_0805T"))
    )
    (comp (ref "R24")
      (value "0.36")
      (footprint "eagle-import:0805T")
      (libsource (lib "eagle-import") (part "R_0805T"))
    )
    (comp (ref "R25")
      (value "0.36")
      (footprint "eagle-import:0805T")
      (libsource (lib "eagle-import") (part "R_0805T"))
    )
    (comp (ref "R26")
      (value "0.36")
      (footprint "eagle-import:0805T")
      (libsource (lib "eagle-import") (part "R_0805T"))
    )
    (comp (ref "R27")
      (value "0.36")
      (footprint "eagle-import:0805T")
      (libsource (lib "eagle-import") (part "R_0805T"))
    )
    (comp (ref "R28")
      (value "0.36")
      (footprint "eagle-import:0805T")
      (libsource (lib "eagle-import") (part "R_0805T"))
    )
    (comp (ref "R29")
      (value "0.36")
      (footprint "eagle-import:0805T")
      (libsource (lib "eagle-import") (part "R_0805T"))
    )
    (comp (ref "R30")
      (value "0.36")
      (footprint "eagle-import:0805T")
      (libsource (lib "eagle-import") (part "R_0805T"))
    )
    (comp (ref "R31")
      (value "0.36")
      (footprint "eagle-import:0805T")
      (libsource (lib "eagle-import") (part "R_0805T"))
    )
    (comp (ref "R32")
      (value "0.36")
      (footprint "eagle-import:0805T")
      (libsource (lib "eagle-import") (part "R_0805T"))
    )
    (comp (ref "R33")
      (value "0.36")
      (footprint "eagle-import:0805T")
      (libsource (lib "eagle-import") (part "R_0805T"))
    )
    (comp (ref "R34")
      (value "0.36")
      (footprint "eagle-import:0805T")
      (libsource (lib "eagle-import") (part "R_0805T"))
    )
    (comp (ref "R35")
      (value "0.36")
      (footprint "eagle-import:0805T")
      (libsource (lib "eagle-import") (part "R_0805T"))
    )
    (comp (ref "R36")
      (value "0.36")
      (footprint "eagle-import:0805T")
      (libsource (lib "eagle-import") (part "R_0805T"))
    )
    (comp (ref "R37")
      (value "0.36")
      (footprint "eagle-import:0805T")
      (libsource (lib "eagle-import") (part "R_0805T"))
    )
    (comp (ref "R38")
      (value "0.36")
      (footprint "eagle-import:0805T")
      (libsource (lib "eagle-import") (part "R_0805T"))
    )
    (comp (ref "R39")
      (value "0.36")
      (footprint "eagle-import:0805T")
      (libsource (lib "eagle-import") (part "R_0805T"))
    )
    (comp (ref "R40")
      (value "0.36")
      (footprint "eagle-import:0805T")
      (libsource (lib "eagle-import") (part "R_0805T"))
    )
    (comp (ref "R41")
      (value "0.36")
      (footprint "eagle-import:0805T")
      (libsource (lib "eagle-import") (part "R_0805T"))
    )
    (comp (ref "R42")
      (value "0.36")
      (footprint "eagle-import:0805T")
      (libsource (lib "eagle-import") (part "R_0805T"))
    )
    (comp (ref "R43")
      (value "0.36")
      (footprint "eagle-import:0805T")
      (libsource (lib "eagle-import") (part "R_0805T"))
    )
    (comp (ref "R44")
      (value "0.36")
      (footprint "eagle-import:0805T")
      (libsource (lib "eagle-import") (part "R_0805T"))
    )
    (comp (ref "R45")
      (value "0.36")
      (footprint "eagle-import:0805T")
      (libsource (lib "eagle-import") (part "R_0805T"))
    )
    (comp (ref "R46")
      (value "0.36")
      (footprint "eagle-import:0805T")
      (libsource (lib "eagle-import") (part "R_0805T"))
    )
    (comp (ref "R47")
      (value "0.36")
      (footprint "eagle-import:0805T")
      (libsource (lib "eagle-import") (part "R_0805T"))
    )
    (comp (ref "R48")
      (value "0.36")
      (footprint "eagle-import:0805T")
      (libsource (lib "eagle-import") (part "R_0805T"))
    )
    (comp (ref "R49")
      (value "10")
      (footprint "eagle-import:0402T")
      (libsource (lib "eagle-import") (part "R_0402T"))
    )
    (comp (ref "R50")
      (value "10")
      (footprint "eagle-import:0402T")
      (libsource (lib "eagle-import") (part "R_0402T"))
    )
    (comp (ref "R51")
      (value "10")
      (footprint "eagle-import:0402T")
      (libsource (lib "eagle-import") (part "R_0402T"))
    )
    (comp (ref "R52")
      (value "0.36")
      (footprint "eagle-import:0805T")
      (libsource (lib "eagle-import") (part "R_0805T"))
    )
    (comp (ref "R53")
      (value "0.36")
      (footprint "eagle-import:0805T")
      (libsource (lib "eagle-import") (part "R_0805T"))
    )
    (comp (ref "R54")
      (value "0.36")
      (footprint "eagle-import:0805T")
      (libsource (lib "eagle-import") (part "R_0805T"))
    )
    (comp (ref "R55")
      (value "0.36")
      (footprint "eagle-import:0805T")
      (libsource (lib "eagle-import") (part "R_0805T"))
    )
    (comp (ref "R56")
      (value "0.36")
      (footprint "eagle-import:0805T")
      (libsource (lib "eagle-import") (part "R_0805T"))
    )
    (comp (ref "R57")
      (value "0.36")
      (footprint "eagle-import:0805T")
      (libsource (lib "eagle-import") (part "R_0805T"))
    )
    (comp (ref "R58")
      (value "0.36")
      (footprint "eagle-import:0805T")
      (libsource (lib "eagle-import") (part "R_0805T"))
    )
    (comp (ref "R59")
      (value "0.36")
      (footprint "eagle-import:0805T")
      (libsource (lib "eagle-import") (part "R_0805T"))
    )
    (comp (ref "R60")
      (value "0.36")
      (footprint "eagle-import:0805T")
      (libsource (lib "eagle-import") (part "R_0805T"))
    )
    (comp (ref "R61")
      (value "0.36")
      (footprint "eagle-import:0805T")
      (libsource (lib "eagle-import") (part "R_0805T"))
    )
    (comp (ref "R62")
      (value "0.36")
      (footprint "eagle-import:0805T")
      (libsource (lib "eagle-import") (part "R_0805T"))
    )
    (comp (ref "R63")
      (value "0.36")
      (footprint "eagle-import:0805T")
      (libsource (lib "eagle-import") (part "R_0805T"))
    )
    (comp (ref "R64")
      (value "0.36")
      (footprint "eagle-import:0805T")
      (libsource (lib "eagle-import") (part "R_0805T"))
    )
    (comp (ref "R65")
      (value "0.36")
      (footprint "eagle-import:0805T")
      (libsource (lib "eagle-import") (part "R_0805T"))
    )
    (comp (ref "R66")
      (value "0.36")
      (footprint "eagle-import:0805T")
      (libsource (lib "eagle-import") (part "R_0805T"))
    )
    (comp (ref "R67")
      (value "0.36")
      (footprint "eagle-import:0805T")
      (libsource (lib "eagle-import") (part "R_0805T"))
    )
    (comp (ref "R68")
      (value "0.36")
      (footprint "eagle-import:0805T")
      (libsource (lib "eagle-import") (part "R_0805T"))
    )
    (comp (ref "R69")
      (value "0.36")
      (footprint "eagle-import:0805T")
      (libsource (lib "eagle-import") (part "R_0805T"))
    )
    (comp (ref "R70")
      (value "0.36")
      (footprint "eagle-import:0805T")
      (libsource (lib "eagle-import") (part "R_0805T"))
    )
    (comp (ref "R71")
      (value "0.36")
      (footprint "eagle-import:0805T")
      (libsource (lib "eagle-import") (part "R_0805T"))
    )
    (comp (ref "R72")
      (value "0.36")
      (footprint "eagle-import:0805T")
      (libsource (lib "eagle-import") (part "R_0805T"))
    )
    (comp (ref "R73")
      (value "0.36")
      (footprint "eagle-import:0805T")
      (libsource (lib "eagle-import") (part "R_0805T"))
    )
    (comp (ref "R74")
      (value "0.36")
      (footprint "eagle-import:0805T")
      (libsource (lib "eagle-import") (part "R_0805T"))
    )
    (comp (ref "R75")
      (value "0.36")
      (footprint "eagle-import:0805T")
      (libsource (lib "eagle-import") (part "R_0805T"))
    )
    (comp (ref "R76")
      (value "0.36")
      (footprint "eagle-import:0805T")
      (libsource (lib "eagle-import") (part "R_0805T"))
    )
    (comp (ref "R77")
      (value "0.36")
      (footprint "eagle-import:0805T")
      (libsource (lib "eagle-import") (part "R_0805T"))
    )
    (comp (ref "R78")
      (value "0.36")
      (footprint "eagle-import:0805T")
      (libsource (lib "eagle-import") (part "R_0805T"))
    )
    (comp (ref "R79")
      (value "0.36")
      (footprint "eagle-import:0805T")
      (libsource (lib "eagle-import") (part "R_0805T"))
    )
    (comp (ref "R80")
      (value "0.36")
      (footprint "eagle-import:0805T")
      (libsource (lib "eagle-import") (part "R_0805T"))
    )
    (comp (ref "R81")
      (value "0.36")
      (footprint "eagle-import:0805T")
      (libsource (lib "eagle-import") (part "R_0805T"))
    )
    (comp (ref "R82")
      (value "10")
      (footprint "eagle-import:0402T")
      (libsource (lib "eagle-import") (part "R_0402T"))
    )
    (comp (ref "R83")
      (value "10")
      (footprint "eagle-import:0402T")
      (libsource (lib "eagle-import") (part "R_0402T"))
    )
    (comp (ref "R84")
      (value "10")
      (footprint "eagle-import:0402T")
      (libsource (lib "eagle-import") (part "R_0402T"))
    )
    (comp (ref "R85")
      (value "0.36")
      (footprint "eagle-import:0805T")
      (libsource (lib "eagle-import") (part "R_0805T"))
    )
    (comp (ref "R86")
      (value "0.36")
      (footprint "eagle-import:0805T")
      (libsource (lib "eagle-import") (part "R_0805T"))
    )
    (comp (ref "R87")
      (value "0.36")
      (footprint "eagle-import:0805T")
      (libsource (lib "eagle-import") (part "R_0805T"))
    )
    (comp (ref "R88")
      (value "0.36")
      (footprint "eagle-import:0805T")
      (libsource (lib "eagle-import") (part "R_0805T"))
    )
    (comp (ref "R89")
      (value "0.36")
      (footprint "eagle-import:0805T")
      (libsource (lib "eagle-import") (part "R_0805T"))
    )
    (comp (ref "R90")
      (value "0.36")
      (footprint "eagle-import:0805T")
      (libsource (lib "eagle-import") (part "R_0805T"))
    )
    (comp (ref "TP1")
      (value "TPTP18SQ")
      (footprint "eagle-import:TP18SQ")
      (libsource (lib "eagle-import") (part "TPTP18SQ"))
    )
    (comp (ref "TP2")
      (value "TPTP18SQ")
      (footprint "eagle-import:TP18SQ")
      (libsource (lib "eagle-import") (part "TPTP18SQ"))
    )
    (comp (ref "U1")
      (value "UCC27517DBVR")
      (footprint "eagle-import:SOT-23-5")
      (libsource (lib "eagle-import") (part "UCC27517_SOT"))
    )
    (comp (ref "U2")
      (value "UCC27517DBVR")
      (footprint "eagle-import:SOT-23-5")
      (libsource (lib "eagle-import") (part "UCC27517_SOT"))
    )
    (comp (ref "U3")
      (value "SN74LVC1G123YZPR")
      (footprint "eagle-import:DSBGA8-1.9X0.9MM")
      (libsource (lib "eagle-import") (part "MONOSTABLE-MULTIVIBRATOR_DSBGA"))
    )
    (comp (ref "U4")
      (value "LTC1693-5")
      (footprint "eagle-import:MSOP-8-3X3")
      (libsource (lib "eagle-import") (part "LTC1693_MSOP"))
    )
    (comp (ref "U5")
      (value "UCC27517DBVR")
      (footprint "eagle-import:SOT-23-5")
      (libsource (lib "eagle-import") (part "UCC27517_SOT"))
    )
    (comp (ref "U6")
      (value "UCC27517DBVR")
      (footprint "eagle-import:SOT-23-5")
      (libsource (lib "eagle-import") (part "UCC27517_SOT"))
    )
    (comp (ref "U7")
      (value "UCC27517DBVR")
      (footprint "eagle-import:SOT-23-5")
      (libsource (lib "eagle-import") (part "UCC27517_SOT"))
    )
    (comp (ref "U8")
      (value "UCC27517DBVR")
      (footprint "eagle-import:SOT-23-5")
      (libsource (lib "eagle-import") (part "UCC27517_SOT"))
    )
    (comp (ref "U9")
      (value "UCC27517DBVR")
      (footprint "eagle-import:SOT-23-5")
      (libsource (lib "eagle-import") (part "UCC27517_SOT"))
    )
    (comp (ref "U10")
      (value "UCC27517DBVR")
      (footprint "eagle-import:SOT-23-5")
      (libsource (lib "eagle-import") (part "UCC27517_SOT"))
    )
  )
  (nets
    (net (code "1") (name "+3V3") (class "Default")
      (node (ref "J1") (pin "26") (pinfunction "26_26") (pintype "bidirectional"))
    )
    (net (code "2") (name "+5V") (class "Default")
      (node (ref "C3") (pin "1") (pinfunction "1_1") (pintype "passive"))
      (node (ref "C33") (pin "1") (pinfunction "1_1") (pintype "passive"))
      (node (ref "C34") (pin "1") (pinfunction "1_1") (pintype "passive"))
      (node (ref "C35") (pin "1") (pinfunction "1_1") (pintype "passive"))
      (node (ref "C39") (pin "1") (pinfunction "1_1") (pintype "passive"))
      (node (ref "C4") (pin "1") (pinfunction "1_1") (pintype "passive"))
      (node (ref "C40") (pin "1") (pinfunction "1_1") (pintype "passive"))
      (node (ref "C41") (pin "1") (pinfunction "1_1") (pintype "passive"))
      (node (ref "C69") (pin "1") (pinfunction "1_1") (pintype "passive"))
      (node (ref "C70") (pin "1") (pinfunction "1_1") (pintype "passive"))
      (node (ref "C71") (pin "1") (pinfunction "1_1") (pintype "passive"))
      (node (ref "C75") (pin "1") (pinfunction "1_1") (pintype "passive"))
      (node (ref "C76") (pin "1") (pinfunction "1_1") (pintype "passive"))
      (node (ref "C77") (pin "1") (pinfunction "1_1") (pintype "passive"))
      (node (ref "C8") (pin "1") (pinfunction "1_1") (pintype "passive"))
      (node (ref "C9") (pin "1") (pinfunction "1_1") (pintype "passive"))
      (node (ref "D31") (pin "4") (pinfunction "A_4") (pintype "passive"))
      (node (ref "J1") (pin "27") (pinfunction "27_27") (pintype "bidirectional"))
      (node (ref "R10") (pin "1") (pinfunction "1_1") (pintype "passive"))
      (node (ref "U1") (pin "1") (pinfunction "VDD_1") (pintype "power_in"))
      (node (ref "U10") (pin "1") (pinfunction "VDD_1") (pintype "power_in"))
      (node (ref "U2") (pin "1") (pinfunction "VDD_1") (pintype "power_in"))
      (node (ref "U3") (pin "A2") (pinfunction "VCC_A2") (pintype "power_in"))
      (node (ref "U3") (pin "C1") (pinfunction "~{CLR}_C1") (pintype "input"))
      (node (ref "U5") (pin "1") (pinfunction "VDD_1") (pintype "power_in"))
      (node (ref "U6") (pin "1") (pinfunction "VDD_1") (pintype "power_in"))
      (node (ref "U7") (pin "1") (pinfunction "VDD_1") (pintype "power_in"))
      (node (ref "U8") (pin "1") (pinfunction "VDD_1") (pintype "power_in"))
      (node (ref "U9") (pin "1") (pinfunction "VDD_1") (pintype "power_in"))
    )
    (net (code "3") (name "+12V") (class "Default")
      (node (ref "C1") (pin "2") (pinfunction "2_2") (pintype "passive"))
      (node (ref "C100") (pin "1") (pinfunction "1_1") (pintype "passive"))
      (node (ref "C101") (pin "1") (pinfunction "1_1") (pintype "passive"))
      (node (ref "C11") (pin "2") (pinfunction "2_2") (pintype "passive"))
      (node (ref "C12") (pin "2") (pinfunction "2_2") (pintype "passive"))
      (node (ref "C13") (pin "2") (pinfunction "2_2") (pintype "passive"))
      (node (ref "C14") (pin "2") (pinfunction "2_2") (pintype "passive"))
      (node (ref "C16") (pin "2") (pinfunction "2_2") (pintype "passive"))
      (node (ref "C17") (pin "2") (pinfunction "2_2") (pintype "passive"))
      (node (ref "C18") (pin "1") (pinfunction "1_1") (pintype "passive"))
      (node (ref "C19") (pin "1") (pinfunction "1_1") (pintype "passive"))
      (node (ref "C2") (pin "2") (pinfunction "2_2") (pintype "passive"))
      (node (ref "C20") (pin "1") (pinfunction "1_1") (pintype "passive"))
      (node (ref "C21") (pin "1") (pinfunction "1_1") (pintype "passive"))
      (node (ref "C22") (pin "1") (pinfunction "1_1") (pintype "passive"))
      (node (ref "C23") (pin "1") (pinfunction "1_1") (pintype "passive"))
      (node (ref "C24") (pin "1") (pinfunction "1_1") (pintype "passive"))
      (node (ref "C25") (pin "1") (pinfunction "1_1") (pintype "passive"))
      (node (ref "C26") (pin "1") (pinfunction "1_1") (pintype "passive"))
      (node (ref "C27") (pin "1") (pinfunction "1_1") (pintype "passive"))
      (node (ref "C28") (pin "A") (pinfunction "+_A") (pintype "passive"))
      (node (ref "C29") (pin "A") (pinfunction "+_A") (pintype "passive"))
      (node (ref "C30") (pin "2") (pinfunction "2_2") (pintype "passive"))
      (node (ref "C31") (pin "2") (pinfunction "2_2") (pintype "passive"))
      (node (ref "C32") (pin "2") (pinfunction "2_2") (pintype "passive"))
      (node (ref "C36") (pin "2") (pinfunction "2_2") (pintype "passive"))
      (node (ref "C37") (pin "2") (pinfunction "2_2") (pintype "passive"))
      (node (ref "C38") (pin "2") (pinfunction "2_2") (pintype "passive"))
      (node (ref "C42") (pin "2") (pinfunction "2_2") (pintype "passive"))
      (node (ref "C43") (pin "2") (pinfunction "2_2") (pintype "passive"))
      (node (ref "C44") (pin "2") (pinfunction "2_2") (pintype "passive"))
      (node (ref "C45") (pin "2") (pinfunction "2_2") (pintype "passive"))
      (node (ref "C46") (pin "2") (pinfunction "2_2") (pintype "passive"))
      (node (ref "C47") (pin "2") (pinfunction "2_2") (pintype "passive"))
      (node (ref "C48") (pin "2") (pinfunction "2_2") (pintype "passive"))
      (node (ref "C49") (pin "2") (pinfunction "2_2") (pintype "passive"))
      (node (ref "C50") (pin "2") (pinfunction "2_2") (pintype "passive"))
      (node (ref "C51") (pin "1") (pinfunction "1_1") (pintype "passive"))
      (node (ref "C52") (pin "1") (pinfunction "1_1") (pintype "passive"))
      (node (ref "C53") (pin "1") (pinfunction "1_1") (pintype "passive"))
      (node (ref "C54") (pin "1") (pinfunction "1_1") (pintype "passive"))
      (node (ref "C55") (pin "1") (pinfunction "1_1") (pintype "passive"))
      (node (ref "C56") (pin "1") (pinfunction "1_1") (pintype "passive"))
      (node (ref "C57") (pin "1") (pinfunction "1_1") (pintype "passive"))
      (node (ref "C58") (pin "1") (pinfunction "1_1") (pintype "passive"))
      (node (ref "C59") (pin "1") (pinfunction "1_1") (pintype "passive"))
      (node (ref "C6") (pin "2") (pinfunction "2_2") (pintype "passive"))
      (node (ref "C60") (pin "1") (pinfunction "1_1") (pintype "passive"))
      (node (ref "C61") (pin "1") (pinfunction "1_1") (pintype "passive"))
      (node (ref "C62") (pin "1") (pinfunction "1_1") (pintype "passive"))
      (node (ref "C63") (pin "1") (pinfunction "1_1") (pintype "passive"))
      (node (ref "C64") (pin "1") (pinfunction "1_1") (pintype "passive"))
      (node (ref "C65") (pin "1") (pinfunction "1_1") (pintype "passive"))
      (node (ref "C66") (pin "2") (pinfunction "2_2") (pintype "passive"))
      (node (ref "C67") (pin "2") (pinfunction "2_2") (pintype "passive"))
      (node (ref "C68") (pin "2") (pinfunction "2_2") (pintype "passive"))
      (node (ref "C7") (pin "2") (pinfunction "2_2") (pintype "passive"))
      (node (ref "C72") (pin "2") (pinfunction "2_2") (pintype "passive"))
      (node (ref "C73") (pin "2") (pinfunction "2_2") (pintype "passive"))
      (node (ref "C74") (pin "2") (pinfunction "2_2") (pintype "passive"))
      (node (ref "C78") (pin "2") (pinfunction "2_2") (pintype "passive"))
      (node (ref "C79") (pin "2") (pinfunction "2_2") (pintype "passive"))
      (node (ref "C80") (pin "2") (pinfunction "2_2") (pintype "passive"))
      (node (ref "C81") (pin "2") (pinfunction "2_2") (pintype "passive"))
      (node (ref "C82") (pin "2") (pinfunction "2_2") (pintype "passive"))
      (node (ref "C83") (pin "2") (pinfunction "2_2") (pintype "passive"))
      (node (ref "C84") (pin "2") (pinfunction "2_2") (pintype "passive"))
      (node (ref "C85") (pin "2") (pinfunction "2_2") (pintype "passive"))
      (node (ref "C86") (pin "1") (pinfunction "1_1") (pintype "passive"))
      (node (ref "C87") (pin "1") (pinfunction "1_1") (pintype "passive"))
      (node (ref "C88") (pin "1") (pinfunction "1_1") (pintype "passive"))
      (node (ref "C89") (pin "1") (pinfunction "1_1") (pintype "passive"))
      (node (ref "C90") (pin "1") (pinfunction "1_1") (pintype "passive"))
      (node (ref "C91") (pin "1") (pinfunction "1_1") (pintype "passive"))
      (node (ref "C92") (pin "1") (pinfunction "1_1") (pintype "passive"))
      (node (ref "C93") (pin "1") (pinfunction "1_1") (pintype "passive"))
      (node (ref "C94") (pin "1") (pinfunction "1_1") (pintype "passive"))
      (node (ref "C95") (pin "1") (pinfunction "1_1") (pintype "passive"))
      (node (ref "C96") (pin "1") (pinfunction "1_1") (pintype "passive"))
      (node (ref "C97") (pin "1") (pinfunction "1_1") (pintype "passive"))
      (node (ref "C98") (pin "1") (pinfunction "1_1") (pintype "passive"))
      (node (ref "C99") (pin "1") (pinfunction "1_1") (pintype "passive"))
      (node (ref "L1") (pin "1") (pinfunction "1_1") (pintype "passive"))
      (node (ref "L10") (pin "1") (pinfunction "1_1") (pintype "passive"))
      (node (ref "L11") (pin "1") (pinfunction "1_1") (pintype "passive"))
      (node (ref "L12") (pin "1") (pinfunction "1_1") (pintype "passive"))
      (node (ref "L13") (pin "1") (pinfunction "1_1") (pintype "passive"))
      (node (ref "L14") (pin "1") (pinfunction "1_1") (pintype "passive"))
      (node (ref "L15") (pin "1") (pinfunction "1_1") (pintype "passive"))
      (node (ref "L16") (pin "1") (pinfunction "1_1") (pintype "passive"))
      (node (ref "L17") (pin "1") (pinfunction "1_1") (pintype "passive"))
      (node (ref "L18") (pin "1") (pinfunction "1_1") (pintype "passive"))
      (node (ref "L19") (pin "1") (pinfunction "1_1") (pintype "passive"))
      (node (ref "L2") (pin "1") (pinfunction "1_1") (pintype "passive"))
      (node (ref "L20") (pin "1") (pinfunction "1_1") (pintype "passive"))
      (node (ref "L21") (pin "1") (pinfunction "1_1") (pintype "passive"))
      (node (ref "L22") (pin "1") (pinfunction "1_1") (pintype "passive"))
      (node (ref "L23") (pin "1") (pinfunction "1_1") (pintype "passive"))
      (node (ref "L24") (pin "1") (pinfunction "1_1") (pintype "passive"))
      (node (ref "L25") (pin "1") (pinfunction "1_1") (pintype "passive"))
      (node (ref "L26") (pin "1") (pinfunction "1_1") (pintype "passive"))
      (node (ref "L27") (pin "1") (pinfunction "1_1") (pintype "passive"))
      (node (ref "L28") (pin "1") (pinfunction "1_1") (pintype "passive"))
      (node (ref "L29") (pin "1") (pinfunction "1_1") (pintype "passive"))
      (node (ref "L3") (pin "1") (pinfunction "1_1") (pintype "passive"))
      (node (ref "L30") (pin "1") (pinfunction "1_1") (pintype "passive"))
      (node (ref "L31") (pin "1") (pinfunction "1_1") (pintype "passive"))
      (node (ref "L32") (pin "1") (pinfunction "1_1") (pintype "passive"))
      (node (ref "L33") (pin "1") (pinfunction "1_1") (pintype "passive"))
      (node (ref "L34") (pin "1") (pinfunction "1_1") (pintype "passive"))
      (node (ref "L35") (pin "1") (pinfunction "1_1") (pintype "passive"))
      (node (ref "L36") (pin "1") (pinfunction "1_1") (pintype "passive"))
      (node (ref "L37") (pin "1") (pinfunction "1_1") (pintype "passive"))
      (node (ref "L38") (pin "1") (pinfunction "1_1") (pintype "passive"))
      (node (ref "L39") (pin "1") (pinfunction "1_1") (pintype "passive"))
      (node (ref "L4") (pin "1") (pinfunction "1_1") (pintype "passive"))
      (node (ref "L40") (pin "1") (pinfunction "1_1") (pintype "passive"))
      (node (ref "L5") (pin "1") (pinfunction "1_1") (pintype "passive"))
      (node (ref "L6") (pin "1") (pinfunction "1_1") (pintype "passive"))
      (node (ref "L7") (pin "1") (pinfunction "1_1") (pintype "passive"))
      (node (ref "L8") (pin "1") (pinfunction "1_1") (pintype "passive"))
      (node (ref "L9") (pin "1") (pinfunction "1_1") (pintype "passive"))
      (node (ref "TP2") (pin "TP") (pinfunction "TP_TP") (pintype "bidirectional"))
    )
    (net (code "4") (name "BLUE_C") (class "Default")
      (node (ref "D31") (pin "3") (pinfunction "CB_3") (pintype "passive"))
      (node (ref "J1") (pin "24") (pinfunction "24_24") (pintype "bidirectional"))
    )
    (net (code "5") (name "DIFF1") (class "Default")
      (node (ref "J1") (pin "17") (pinfunction "17_17") (pintype "bidirectional"))
    )
    (net (code "6") (name "DIFF2") (class "Default")
      (node (ref "J1") (pin "18") (pinfunction "18_18") (pintype "bidirectional"))
    )
    (net (code "7") (name "GND") (class "Default")
      (node (ref "C1") (pin "1") (pinfunction "1_1") (pintype "passive"))
      (node (ref "C10") (pin "2") (pinfunction "2_2") (pintype "passive"))
      (node (ref "C100") (pin "2") (pinfunction "2_2") (pintype "passive"))
      (node (ref "C101") (pin "2") (pinfunction "2_2") (pintype "passive"))
      (node (ref "C11") (pin "1") (pinfunction "1_1") (pintype "passive"))
      (node (ref "C12") (pin "1") (pinfunction "1_1") (pintype "passive"))
      (node (ref "C13") (pin "1") (pinfunction "1_1") (pintype "passive"))
      (node (ref "C14") (pin "1") (pinfunction "1_1") (pintype "passive"))
      (node (ref "C16") (pin "1") (pinfunction "1_1") (pintype "passive"))
      (node (ref "C17") (pin "1") (pinfunction "1_1") (pintype "passive"))
      (node (ref "C18") (pin "2") (pinfunction "2_2") (pintype "passive"))
      (node (ref "C19") (pin "2") (pinfunction "2_2") (pintype "passive"))
      (node (ref "C2") (pin "1") (pinfunction "1_1") (pintype "passive"))
      (node (ref "C20") (pin "2") (pinfunction "2_2") (pintype "passive"))
      (node (ref "C21") (pin "2") (pinfunction "2_2") (pintype "passive"))
      (node (ref "C22") (pin "2") (pinfunction "2_2") (pintype "passive"))
      (node (ref "C23") (pin "2") (pinfunction "2_2") (pintype "passive"))
      (node (ref "C24") (pin "2") (pinfunction "2_2") (pintype "passive"))
      (node (ref "C25") (pin "2") (pinfunction "2_2") (pintype "passive"))
      (node (ref "C26") (pin "2") (pinfunction "2_2") (pintype "passive"))
      (node (ref "C27") (pin "2") (pinfunction "2_2") (pintype "passive"))
      (node (ref "C28") (pin "C") (pinfunction "-_C") (pintype "passive"))
      (node (ref "C29") (pin "C") (pinfunction "-_C") (pintype "passive"))
      (node (ref "C3") (pin "2") (pinfunction "2_2") (pintype "passive"))
      (node (ref "C30") (pin "1") (pinfunction "1_1") (pintype "passive"))
      (node (ref "C31") (pin "1") (pinfunction "1_1") (pintype "passive"))
      (node (ref "C32") (pin "1") (pinfunction "1_1") (pintype "passive"))
      (node (ref "C33") (pin "2") (pinfunction "2_2") (pintype "passive"))
      (node (ref "C34") (pin "2") (pinfunction "2_2") (pintype "passive"))
      (node (ref "C35") (pin "2") (pinfunction "2_2") (pintype "passive"))
      (node (ref "C36") (pin "1") (pinfunction "1_1") (pintype "passive"))
      (node (ref "C37") (pin "1") (pinfunction "1_1") (pintype "passive"))
      (node (ref "C38") (pin "1") (pinfunction "1_1") (pintype "passive"))
      (node (ref "C39") (pin "2") (pinfunction "2_2") (pintype "passive"))
      (node (ref "C4") (pin "2") (pinfunction "2_2") (pintype "passive"))
      (node (ref "C40") (pin "2") (pinfunction "2_2") (pintype "passive"))
      (node (ref "C41") (pin "2") (pinfunction "2_2") (pintype "passive"))
      (node (ref "C42") (pin "1") (pinfunction "1_1") (pintype "passive"))
      (node (ref "C43") (pin "1") (pinfunction "1_1") (pintype "passive"))
      (node (ref "C44") (pin "1") (pinfunction "1_1") (pintype "passive"))
      (node (ref "C45") (pin "1") (pinfunction "1_1") (pintype "passive"))
      (node (ref "C46") (pin "1") (pinfunction "1_1") (pintype "passive"))
      (node (ref "C47") (pin "1") (pinfunction "1_1") (pintype "passive"))
      (node (ref "C48") (pin "1") (pinfunction "1_1") (pintype "passive"))
      (node (ref "C49") (pin "1") (pinfunction "1_1") (pintype "passive"))
      (node (ref "C5") (pin "2") (pinfunction "2_2") (pintype "passive"))
      (node (ref "C50") (pin "1") (pinfunction "1_1") (pintype "passive"))
      (node (ref "C51") (pin "2") (pinfunction "2_2") (pintype "passive"))
      (node (ref "C52") (pin "2") (pinfunction "2_2") (pintype "passive"))
      (node (ref "C53") (pin "2") (pinfunction "2_2") (pintype "passive"))
      (node (ref "C54") (pin "2") (pinfunction "2_2") (pintype "passive"))
      (node (ref "C55") (pin "2") (pinfunction "2_2") (pintype "passive"))
      (node (ref "C56") (pin "2") (pinfunction "2_2") (pintype "passive"))
      (node (ref "C57") (pin "2") (pinfunction "2_2") (pintype "passive"))
      (node (ref "C58") (pin "2") (pinfunction "2_2") (pintype "passive"))
      (node (ref "C59") (pin "2") (pinfunction "2_2") (pintype "passive"))
      (node (ref "C6") (pin "1") (pinfunction "1_1") (pintype "passive"))
      (node (ref "C60") (pin "2") (pinfunction "2_2") (pintype "passive"))
      (node (ref "C61") (pin "2") (pinfunction "2_2") (pintype "passive"))
      (node (ref "C62") (pin "2") (pinfunction "2_2") (pintype "passive"))
      (node (ref "C63") (pin "2") (pinfunction "2_2") (pintype "passive"))
      (node (ref "C64") (pin "2") (pinfunction "2_2") (pintype "passive"))
      (node (ref "C65") (pin "2") (pinfunction "2_2") (pintype "passive"))
      (node (ref "C66") (pin "1") (pinfunction "1_1") (pintype "passive"))
      (node (ref "C67") (pin "1") (pinfunction "1_1") (pintype "passive"))
      (node (ref "C68") (pin "1") (pinfunction "1_1") (pintype "passive"))
      (node (ref "C69") (pin "2") (pinfunction "2_2") (pintype "passive"))
      (node (ref "C7") (pin "1") (pinfunction "1_1") (pintype "passive"))
      (node (ref "C70") (pin "2") (pinfunction "2_2") (pintype "passive"))
      (node (ref "C71") (pin "2") (pinfunction "2_2") (pintype "passive"))
      (node (ref "C72") (pin "1") (pinfunction "1_1") (pintype "passive"))
      (node (ref "C73") (pin "1") (pinfunction "1_1") (pintype "passive"))
      (node (ref "C74") (pin "1") (pinfunction "1_1") (pintype "passive"))
      (node (ref "C75") (pin "2") (pinfunction "2_2") (pintype "passive"))
      (node (ref "C76") (pin "2") (pinfunction "2_2") (pintype "passive"))
      (node (ref "C77") (pin "2") (pinfunction "2_2") (pintype "passive"))
      (node (ref "C78") (pin "1") (pinfunction "1_1") (pintype "passive"))
      (node (ref "C79") (pin "1") (pinfunction "1_1") (pintype "passive"))
      (node (ref "C8") (pin "2") (pinfunction "2_2") (pintype "passive"))
      (node (ref "C80") (pin "1") (pinfunction "1_1") (pintype "passive"))
      (node (ref "C81") (pin "1") (pinfunction "1_1") (pintype "passive"))
      (node (ref "C82") (pin "1") (pinfunction "1_1") (pintype "passive"))
      (node (ref "C83") (pin "1") (pinfunction "1_1") (pintype "passive"))
      (node (ref "C84") (pin "1") (pinfunction "1_1") (pintype "passive"))
      (node (ref "C85") (pin "1") (pinfunction "1_1") (pintype "passive"))
      (node (ref "C86") (pin "2") (pinfunction "2_2") (pintype "passive"))
      (node (ref "C87") (pin "2") (pinfunction "2_2") (pintype "passive"))
      (node (ref "C88") (pin "2") (pinfunction "2_2") (pintype "passive"))
      (node (ref "C89") (pin "2") (pinfunction "2_2") (pintype "passive"))
      (node (ref "C9") (pin "2") (pinfunction "2_2") (pintype "passive"))
      (node (ref "C90") (pin "2") (pinfunction "2_2") (pintype "passive"))
      (node (ref "C91") (pin "2") (pinfunction "2_2") (pintype "passive"))
      (node (ref "C92") (pin "2") (pinfunction "2_2") (pintype "passive"))
      (node (ref "C93") (pin "2") (pinfunction "2_2") (pintype "passive"))
      (node (ref "C94") (pin "2") (pinfunction "2_2") (pintype "passive"))
      (node (ref "C95") (pin "2") (pinfunction "2_2") (pintype "passive"))
      (node (ref "C96") (pin "2") (pinfunction "2_2") (pintype "passive"))
      (node (ref "C97") (pin "2") (pinfunction "2_2") (pintype "passive"))
      (node (ref "C98") (pin "2") (pinfunction "2_2") (pintype "passive"))
      (node (ref "C99") (pin "2") (pinfunction "2_2") (pintype "passive"))
      (node (ref "J1") (pin "1") (pinfunction "1_1") (pintype "bidirectional"))
      (node (ref "J1") (pin "12") (pinfunction "12_12") (pintype "bidirectional"))
      (node (ref "J1") (pin "13") (pinfunction "13_13") (pintype "bidirectional"))
      (node (ref "J1") (pin "14") (pinfunction "14_14") (pintype "bidirectional"))
      (node (ref "J1") (pin "15") (pinfunction "15_15") (pintype "bidirectional"))
      (node (ref "J1") (pin "19") (pinfunction "19_19") (pintype "bidirectional"))
      (node (ref "J1") (pin "21") (pinfunction "21_21") (pintype "bidirectional"))
      (node (ref "J1") (pin "25") (pinfunction "25_25") (pintype "bidirectional"))
      (node (ref "J1") (pin "28") (pinfunction "28_28") (pintype "bidirectional"))
      (node (ref "Q1") (pin "1") (pinfunction "S_1") (pintype "bidirectional"))
      (node (ref "Q1") (pin "2") (pinfunction "S_2") (pintype "bidirectional"))
      (node (ref "Q1") (pin "3") (pinfunction "S_3") (pintype "bidirectional"))
      (node (ref "Q2") (pin "1") (pinfunction "S_1") (pintype "bidirectional"))
      (node (ref "Q2") (pin "2") (pinfunction "S_2") (pintype "bidirectional"))
      (node (ref "Q2") (pin "3") (pinfunction "S_3") (pintype "bidirectional"))
      (node (ref "Q4") (pin "1") (pinfunction "S_1") (pintype "bidirectional"))
      (node (ref "Q4") (pin "2") (pinfunction "S_2") (pintype "bidirectional"))
      (node (ref "Q4") (pin "3") (pinfunction "S_3") (pintype "bidirectional"))
      (node (ref "Q5") (pin "1") (pinfunction "S_1") (pintype "bidirectional"))
      (node (ref "Q5") (pin "2") (pinfunction "S_2") (pintype "bidirectional"))
      (node (ref "Q5") (pin "3") (pinfunction "S_3") (pintype "bidirectional"))
      (node (ref "Q6") (pin "1") (pinfunction "S_1") (pintype "bidirectional"))
      (node (ref "Q6") (pin "2") (pinfunction "S_2") (pintype "bidirectional"))
      (node (ref "Q6") (pin "3") (pinfunction "S_3") (pintype "bidirectional"))
      (node (ref "Q7") (pin "1") (pinfunction "S_1") (pintype "bidirectional"))
      (node (ref "Q7") (pin "2") (pinfunction "S_2") (pintype "bidirectional"))
      (node (ref "Q7") (pin "3") (pinfunction "S_3") (pintype "bidirectional"))
      (node (ref "Q8") (pin "1") (pinfunction "S_1") (pintype "bidirectional"))
      (node (ref "Q8") (pin "2") (pinfunction "S_2") (pintype "bidirectional"))
      (node (ref "Q8") (pin "3") (pinfunction "S_3") (pintype "bidirectional"))
      (node (ref "Q9") (pin "1") (pinfunction "S_1") (pintype "bidirectional"))
      (node (ref "Q9") (pin "2") (pinfunction "S_2") (pintype "bidirectional"))
      (node (ref "Q9") (pin "3") (pinfunction "S_3") (pintype "bidirectional"))
      (node (ref "R5") (pin "1") (pinfunction "1_1") (pintype "passive"))
      (node (ref "U1") (pin "2") (pinfunction "GND_2") (pintype "power_in"))
      (node (ref "U1") (pin "4") (pinfunction "IN-_4") (pintype "input"))
      (node (ref "U10") (pin "2") (pinfunction "GND_2") (pintype "power_in"))
      (node (ref "U10") (pin "4") (pinfunction "IN-_4") (pintype "input"))
      (node (ref "U2") (pin "2") (pinfunction "GND_2") (pintype "power_in"))
      (node (ref "U2") (pin "4") (pinfunction "IN-_4") (pintype "input"))
      (node (ref "U3") (pin "A1") (pinfunction "~{A}_A1") (pintype "input"))
      (node (ref "U3") (pin "D1") (pinfunction "GND_D1") (pintype "power_in"))
      (node (ref "U4") (pin "4") (pinfunction "GND_4") (pintype "power_in"))
      (node (ref "U5") (pin "2") (pinfunction "GND_2") (pintype "power_in"))
      (node (ref "U5") (pin "4") (pinfunction "IN-_4") (pintype "input"))
      (node (ref "U6") (pin "2") (pinfunction "GND_2") (pintype "power_in"))
      (node (ref "U6") (pin "4") (pinfunction "IN-_4") (pintype "input"))
      (node (ref "U7") (pin "2") (pinfunction "GND_2") (pintype "power_in"))
      (node (ref "U7") (pin "4") (pinfunction "IN-_4") (pintype "input"))
      (node (ref "U8") (pin "2") (pinfunction "GND_2") (pintype "power_in"))
      (node (ref "U8") (pin "4") (pinfunction "IN-_4") (pintype "input"))
      (node (ref "U9") (pin "2") (pinfunction "GND_2") (pintype "power_in"))
      (node (ref "U9") (pin "4") (pinfunction "IN-_4") (pintype "input"))
    )
    (net (code "8") (name "GREEN_C") (class "Default")
      (node (ref "D31") (pin "2") (pinfunction "CG_2") (pintype "passive"))
      (node (ref "J1") (pin "23") (pinfunction "23_23") (pintype "bidirectional"))
    )
    (net (code "9") (name "N$24") (class "Default")
      (node (ref "R50") (pin "1") (pinfunction "1_1") (pintype "passive"))
      (node (ref "U3") (pin "B1") (pinfunction "B_B1") (pintype "input"))
      (node (ref "U5") (pin "5") (pinfunction "OUT_5") (pintype "output"))
    )
    (net (code "10") (name "Net-(D2-A-PadA1)") (class "Default")
      (node (ref "D2") (pin "A1") (pinfunction "A_A1") (pintype "passive"))
      (node (ref "D2") (pin "A2") (pinfunction "A_A2") (pintype "passive"))
      (node (ref "L1") (pin "2") (pinfunction "2_2") (pintype "passive"))
    )
    (net (code "11") (name "Net-(D2-PadC)") (class "Default")
      (node (ref "D2") (pin "C") (pinfunction "C_C") (pintype "passive"))
      (node (ref "D3") (pin "A1") (pinfunction "A_A1") (pintype "passive"))
      (node (ref "D3") (pin "A2") (pinfunction "A_A2") (pintype "passive"))
    )
    (net (code "12") (name "Net-(D3-PadC)") (class "Default")
      (node (ref "D3") (pin "C") (pinfunction "C_C") (pintype "passive"))
      (node (ref "R1") (pin "2") (pinfunction "2_2") (pintype "passive"))
      (node (ref "R3") (pin "2") (pinfunction "2_2") (pintype "passive"))
    )
    (net (code "13") (name "Net-(D5-A-PadA1)") (class "Default")
      (node (ref "D5") (pin "A1") (pinfunction "A_A1") (pintype "passive"))
      (node (ref "D5") (pin "A2") (pinfunction "A_A2") (pintype "passive"))
      (node (ref "L16") (pin "2") (pinfunction "2_2") (pintype "passive"))
    )
    (net (code "14") (name "Net-(D5-PadC)") (class "Default")
      (node (ref "D5") (pin "C") (pinfunction "C_C") (pintype "passive"))
      (node (ref "D6") (pin "A1") (pinfunction "A_A1") (pintype "passive"))
      (node (ref "D6") (pin "A2") (pinfunction "A_A2") (pintype "passive"))
    )
    (net (code "15") (name "Net-(D6-PadC)") (class "Default")
      (node (ref "D6") (pin "C") (pinfunction "C_C") (pintype "passive"))
      (node (ref "R2") (pin "2") (pinfunction "2_2") (pintype "passive"))
      (node (ref "R4") (pin "2") (pinfunction "2_2") (pintype "passive"))
    )
    (net (code "16") (name "Net-(D8-A-PadA1)") (class "Default")
      (node (ref "D8") (pin "A1") (pinfunction "A_A1") (pintype "passive"))
      (node (ref "D8") (pin "A2") (pinfunction "A_A2") (pintype "passive"))
      (node (ref "L2") (pin "2") (pinfunction "2_2") (pintype "passive"))
    )
    (net (code "17") (name "Net-(D8-PadC)") (class "Default")
      (node (ref "D8") (pin "C") (pinfunction "C_C") (pintype "passive"))
      (node (ref "D9") (pin "A1") (pinfunction "A_A1") (pintype "passive"))
      (node (ref "D9") (pin "A2") (pinfunction "A_A2") (pintype "passive"))
    )
    (net (code "18") (name "Net-(D9-PadC)") (class "Default")
      (node (ref "D9") (pin "C") (pinfunction "C_C") (pintype "passive"))
      (node (ref "R6") (pin "2") (pinfunction "2_2") (pintype "passive"))
      (node (ref "R8") (pin "2") (pinfunction "2_2") (pintype "passive"))
    )
    (net (code "19") (name "Net-(D11-A-PadA1)") (class "Default")
      (node (ref "D11") (pin "A1") (pinfunction "A_A1") (pintype "passive"))
      (node (ref "D11") (pin "A2") (pinfunction "A_A2") (pintype "passive"))
      (node (ref "L17") (pin "2") (pinfunction "2_2") (pintype "passive"))
    )
    (net (code "20") (name "Net-(D11-PadC)") (class "Default")
      (node (ref "D11") (pin "C") (pinfunction "C_C") (pintype "passive"))
      (node (ref "D12") (pin "A1") (pinfunction "A_A1") (pintype "passive"))
      (node (ref "D12") (pin "A2") (pinfunction "A_A2") (pintype "passive"))
    )
    (net (code "21") (name "Net-(D12-PadC)") (class "Default")
      (node (ref "D12") (pin "C") (pinfunction "C_C") (pintype "passive"))
      (node (ref "R7") (pin "2") (pinfunction "2_2") (pintype "passive"))
      (node (ref "R9") (pin "2") (pinfunction "2_2") (pintype "passive"))
    )
    (net (code "22") (name "Net-(D14-A-PadA1)") (class "Default")
      (node (ref "D14") (pin "A1") (pinfunction "A_A1") (pintype "passive"))
      (node (ref "D14") (pin "A2") (pinfunction "A_A2") (pintype "passive"))
      (node (ref "L3") (pin "2") (pinfunction "2_2") (pintype "passive"))
    )
    (net (code "23") (name "Net-(D14-PadC)") (class "Default")
      (node (ref "D14") (pin "C") (pinfunction "C_C") (pintype "passive"))
      (node (ref "D15") (pin "A1") (pinfunction "A_A1") (pintype "passive"))
      (node (ref "D15") (pin "A2") (pinfunction "A_A2") (pintype "passive"))
    )
    (net (code "24") (name "Net-(D15-PadC)") (class "Default")
      (node (ref "D15") (pin "C") (pinfunction "C_C") (pintype "passive"))
      (node (ref "R11") (pin "2") (pinfunction "2_2") (pintype "passive"))
      (node (ref "R13") (pin "2") (pinfunction "2_2") (pintype "passive"))
    )
    (net (code "25") (name "Net-(D17-A-PadA1)") (class "Default")
      (node (ref "D17") (pin "A1") (pinfunction "A_A1") (pintype "passive"))
      (node (ref "D17") (pin "A2") (pinfunction "A_A2") (pintype "passive"))
      (node (ref "L18") (pin "2") (pinfunction "2_2") (pintype "passive"))
    )
    (net (code "26") (name "Net-(D17-PadC)") (class "Default")
      (node (ref "D17") (pin "C") (pinfunction "C_C") (pintype "passive"))
      (node (ref "D18") (pin "A1") (pinfunction "A_A1") (pintype "passive"))
      (node (ref "D18") (pin "A2") (pinfunction "A_A2") (pintype "passive"))
    )
    (net (code "27") (name "Net-(D18-PadC)") (class "Default")
      (node (ref "D18") (pin "C") (pinfunction "C_C") (pintype "passive"))
      (node (ref "R12") (pin "2") (pinfunction "2_2") (pintype "passive"))
      (node (ref "R14") (pin "2") (pinfunction "2_2") (pintype "passive"))
    )
    (net (code "28") (name "Net-(D20-A-PadA1)") (class "Default")
      (node (ref "D20") (pin "A1") (pinfunction "A_A1") (pintype "passive"))
      (node (ref "D20") (pin "A2") (pinfunction "A_A2") (pintype "passive"))
      (node (ref "L4") (pin "2") (pinfunction "2_2") (pintype "passive"))
    )
    (net (code "29") (name "Net-(D20-PadC)") (class "Default")
      (node (ref "D20") (pin "C") (pinfunction "C_C") (pintype "passive"))
      (node (ref "D21") (pin "A1") (pinfunction "A_A1") (pintype "passive"))
      (node (ref "D21") (pin "A2") (pinfunction "A_A2") (pintype "passive"))
    )
    (net (code "30") (name "Net-(D21-PadC)") (class "Default")
      (node (ref "D21") (pin "C") (pinfunction "C_C") (pintype "passive"))
      (node (ref "R15") (pin "2") (pinfunction "2_2") (pintype "passive"))
      (node (ref "R17") (pin "2") (pinfunction "2_2") (pintype "passive"))
    )
    (net (code "31") (name "Net-(D23-A-PadA1)") (class "Default")
      (node (ref "D23") (pin "A1") (pinfunction "A_A1") (pintype "passive"))
      (node (ref "D23") (pin "A2") (pinfunction "A_A2") (pintype "passive"))
      (node (ref "L19") (pin "2") (pinfunction "2_2") (pintype "passive"))
    )
    (net (code "32") (name "Net-(D23-PadC)") (class "Default")
      (node (ref "D23") (pin "C") (pinfunction "C_C") (pintype "passive"))
      (node (ref "D24") (pin "A1") (pinfunction "A_A1") (pintype "passive"))
      (node (ref "D24") (pin "A2") (pinfunction "A_A2") (pintype "passive"))
    )
    (net (code "33") (name "Net-(D24-PadC)") (class "Default")
      (node (ref "D24") (pin "C") (pinfunction "C_C") (pintype "passive"))
      (node (ref "R16") (pin "2") (pinfunction "2_2") (pintype "passive"))
      (node (ref "R18") (pin "2") (pinfunction "2_2") (pintype "passive"))
    )
    (net (code "34") (name "Net-(D26-A-PadA1)") (class "Default")
      (node (ref "D26") (pin "A1") (pinfunction "A_A1") (pintype "passive"))
      (node (ref "D26") (pin "A2") (pinfunction "A_A2") (pintype "passive"))
      (node (ref "L5") (pin "2") (pinfunction "2_2") (pintype "passive"))
    )
    (net (code "35") (name "Net-(D26-PadC)") (class "Default")
      (node (ref "D26") (pin "C") (pinfunction "C_C") (pintype "passive"))
      (node (ref "D27") (pin "A1") (pinfunction "A_A1") (pintype "passive"))
      (node (ref "D27") (pin "A2") (pinfunction "A_A2") (pintype "passive"))
    )
    (net (code "36") (name "Net-(D27-PadC)") (class "Default")
      (node (ref "D27") (pin "C") (pinfunction "C_C") (pintype "passive"))
      (node (ref "R21") (pin "2") (pinfunction "2_2") (pintype "passive"))
      (node (ref "R23") (pin "2") (pinfunction "2_2") (pintype "passive"))
    )
    (net (code "37") (name "Net-(D29-A-PadA1)") (class "Default")
      (node (ref "D29") (pin "A1") (pinfunction "A_A1") (pintype "passive"))
      (node (ref "D29") (pin "A2") (pinfunction "A_A2") (pintype "passive"))
      (node (ref "L20") (pin "2") (pinfunction "2_2") (pintype "passive"))
    )
    (net (code "38") (name "Net-(D29-PadC)") (class "Default")
      (node (ref "D29") (pin "C") (pinfunction "C_C") (pintype "passive"))
      (node (ref "D30") (pin "A1") (pinfunction "A_A1") (pintype "passive"))
      (node (ref "D30") (pin "A2") (pinfunction "A_A2") (pintype "passive"))
    )
    (net (code "39") (name "Net-(D30-PadC)") (class "Default")
      (node (ref "D30") (pin "C") (pinfunction "C_C") (pintype "passive"))
      (node (ref "R22") (pin "2") (pinfunction "2_2") (pintype "passive"))
      (node (ref "R24") (pin "2") (pinfunction "2_2") (pintype "passive"))
    )
    (net (code "40") (name "Net-(D33-A-PadA1)") (class "Default")
      (node (ref "D33") (pin "A1") (pinfunction "A_A1") (pintype "passive"))
      (node (ref "D33") (pin "A2") (pinfunction "A_A2") (pintype "passive"))
      (node (ref "L6") (pin "2") (pinfunction "2_2") (pintype "passive"))
    )
    (net (code "41") (name "Net-(D33-PadC)") (class "Default")
      (node (ref "D33") (pin "C") (pinfunction "C_C") (pintype "passive"))
      (node (ref "D34") (pin "A1") (pinfunction "A_A1") (pintype "passive"))
      (node (ref "D34") (pin "A2") (pinfunction "A_A2") (pintype "passive"))
    )
    (net (code "42") (name "Net-(D34-PadC)") (class "Default")
      (node (ref "D34") (pin "C") (pinfunction "C_C") (pintype "passive"))
      (node (ref "R25") (pin "2") (pinfunction "2_2") (pintype "passive"))
      (node (ref "R28") (pin "2") (pinfunction "2_2") (pintype "passive"))
    )
    (net (code "43") (name "Net-(D36-A-PadA1)") (class "Default")
      (node (ref "D36") (pin "A1") (pinfunction "A_A1") (pintype "passive"))
      (node (ref "D36") (pin "A2") (pinfunction "A_A2") (pintype "passive"))
      (node (ref "L21") (pin "2") (pinfunction "2_2") (pintype "passive"))
    )
    (net (code "44") (name "Net-(D36-PadC)") (class "Default")
      (node (ref "D36") (pin "C") (pinfunction "C_C") (pintype "passive"))
      (node (ref "D37") (pin "A1") (pinfunction "A_A1") (pintype "passive"))
      (node (ref "D37") (pin "A2") (pinfunction "A_A2") (pintype "passive"))
    )
    (net (code "45") (name "Net-(D37-PadC)") (class "Default")
      (node (ref "D37") (pin "C") (pinfunction "C_C") (pintype "passive"))
      (node (ref "R26") (pin "2") (pinfunction "2_2") (pintype "passive"))
      (node (ref "R29") (pin "2") (pinfunction "2_2") (pintype "passive"))
    )
    (net (code "46") (name "Net-(D39-A-PadA1)") (class "Default")
      (node (ref "D39") (pin "A1") (pinfunction "A_A1") (pintype "passive"))
      (node (ref "D39") (pin "A2") (pinfunction "A_A2") (pintype "passive"))
      (node (ref "L31") (pin "2") (pinfunction "2_2") (pintype "passive"))
    )
    (net (code "47") (name "Net-(D39-PadC)") (class "Default")
      (node (ref "D39") (pin "C") (pinfunction "C_C") (pintype "passive"))
      (node (ref "D40") (pin "A1") (pinfunction "A_A1") (pintype "passive"))
      (node (ref "D40") (pin "A2") (pinfunction "A_A2") (pintype "passive"))
    )
    (net (code "48") (name "Net-(D40-PadC)") (class "Default")
      (node (ref "D40") (pin "C") (pinfunction "C_C") (pintype "passive"))
      (node (ref "R27") (pin "2") (pinfunction "2_2") (pintype "passive"))
      (node (ref "R30") (pin "2") (pinfunction "2_2") (pintype "passive"))
    )
    (net (code "49") (name "Net-(D42-A-PadA1)") (class "Default")
      (node (ref "D42") (pin "A1") (pinfunction "A_A1") (pintype "passive"))
      (node (ref "D42") (pin "A2") (pinfunction "A_A2") (pintype "passive"))
      (node (ref "L7") (pin "2") (pinfunction "2_2") (pintype "passive"))
    )
    (net (code "50") (name "Net-(D42-PadC)") (class "Default")
      (node (ref "D42") (pin "C") (pinfunction "C_C") (pintype "passive"))
      (node (ref "D43") (pin "A1") (pinfunction "A_A1") (pintype "passive"))
      (node (ref "D43") (pin "A2") (pinfunction "A_A2") (pintype "passive"))
    )
    (net (code "51") (name "Net-(D43-PadC)") (class "Default")
      (node (ref "D43") (pin "C") (pinfunction "C_C") (pintype "passive"))
      (node (ref "R31") (pin "2") (pinfunction "2_2") (pintype "passive"))
      (node (ref "R34") (pin "2") (pinfunction "2_2") (pintype "passive"))
    )
    (net (code "52") (name "Net-(D45-A-PadA1)") (class "Default")
      (node (ref "D45") (pin "A1") (pinfunction "A_A1") (pintype "passive"))
      (node (ref "D45") (pin "A2") (pinfunction "A_A2") (pintype "passive"))
      (node (ref "L22") (pin "2") (pinfunction "2_2") (pintype "passive"))
    )
    (net (code "53") (name "Net-(D45-PadC)") (class "Default")
      (node (ref "D45") (pin "C") (pinfunction "C_C") (pintype "passive"))
      (node (ref "D46") (pin "A1") (pinfunction "A_A1") (pintype "passive"))
      (node (ref "D46") (pin "A2") (pinfunction "A_A2") (pintype "passive"))
    )
    (net (code "54") (name "Net-(D46-PadC)") (class "Default")
      (node (ref "D46") (pin "C") (pinfunction "C_C") (pintype "passive"))
      (node (ref "R32") (pin "2") (pinfunction "2_2") (pintype "passive"))
      (node (ref "R35") (pin "2") (pinfunction "2_2") (pintype "passive"))
    )
    (net (code "55") (name "Net-(D48-A-PadA1)") (class "Default")
      (node (ref "D48") (pin "A1") (pinfunction "A_A1") (pintype "passive"))
      (node (ref "D48") (pin "A2") (pinfunction "A_A2") (pintype "passive"))
      (node (ref "L32") (pin "2") (pinfunction "2_2") (pintype "passive"))
    )
    (net (code "56") (name "Net-(D48-PadC)") (class "Default")
      (node (ref "D48") (pin "C") (pinfunction "C_C") (pintype "passive"))
      (node (ref "D49") (pin "A1") (pinfunction "A_A1") (pintype "passive"))
      (node (ref "D49") (pin "A2") (pinfunction "A_A2") (pintype "passive"))
    )
    (net (code "57") (name "Net-(D49-PadC)") (class "Default")
      (node (ref "D49") (pin "C") (pinfunction "C_C") (pintype "passive"))
      (node (ref "R33") (pin "2") (pinfunction "2_2") (pintype "passive"))
      (node (ref "R36") (pin "2") (pinfunction "2_2") (pintype "passive"))
    )
    (net (code "58") (name "Net-(D51-A-PadA1)") (class "Default")
      (node (ref "D51") (pin "A1") (pinfunction "A_A1") (pintype "passive"))
      (node (ref "D51") (pin "A2") (pinfunction "A_A2") (pintype "passive"))
      (node (ref "L8") (pin "2") (pinfunction "2_2") (pintype "passive"))
    )
    (net (code "59") (name "Net-(D51-PadC)") (class "Default")
      (node (ref "D51") (pin "C") (pinfunction "C_C") (pintype "passive"))
      (node (ref "D52") (pin "A1") (pinfunction "A_A1") (pintype "passive"))
      (node (ref "D52") (pin "A2") (pinfunction "A_A2") (pintype "passive"))
    )
    (net (code "60") (name "Net-(D52-PadC)") (class "Default")
      (node (ref "D52") (pin "C") (pinfunction "C_C") (pintype "passive"))
      (node (ref "R37") (pin "2") (pinfunction "2_2") (pintype "passive"))
      (node (ref "R40") (pin "2") (pinfunction "2_2") (pintype "passive"))
    )
    (net (code "61") (name "Net-(D54-A-PadA1)") (class "Default")
      (node (ref "D54") (pin "A1") (pinfunction "A_A1") (pintype "passive"))
      (node (ref "D54") (pin "A2") (pinfunction "A_A2") (pintype "passive"))
      (node (ref "L23") (pin "2") (pinfunction "2_2") (pintype "passive"))
    )
    (net (code "62") (name "Net-(D54-PadC)") (class "Default")
      (node (ref "D54") (pin "C") (pinfunction "C_C") (pintype "passive"))
      (node (ref "D55") (pin "A1") (pinfunction "A_A1") (pintype "passive"))
      (node (ref "D55") (pin "A2") (pinfunction "A_A2") (pintype "passive"))
    )
    (net (code "63") (name "Net-(D55-PadC)") (class "Default")
      (node (ref "D55") (pin "C") (pinfunction "C_C") (pintype "passive"))
      (node (ref "R38") (pin "2") (pinfunction "2_2") (pintype "passive"))
      (node (ref "R41") (pin "2") (pinfunction "2_2") (pintype "passive"))
    )
    (net (code "64") (name "Net-(D57-A-PadA1)") (class "Default")
      (node (ref "D57") (pin "A1") (pinfunction "A_A1") (pintype "passive"))
      (node (ref "D57") (pin "A2") (pinfunction "A_A2") (pintype "passive"))
      (node (ref "L33") (pin "2") (pinfunction "2_2") (pintype "passive"))
    )
    (net (code "65") (name "Net-(D57-PadC)") (class "Default")
      (node (ref "D57") (pin "C") (pinfunction "C_C") (pintype "passive"))
      (node (ref "D58") (pin "A1") (pinfunction "A_A1") (pintype "passive"))
      (node (ref "D58") (pin "A2") (pinfunction "A_A2") (pintype "passive"))
    )
    (net (code "66") (name "Net-(D58-PadC)") (class "Default")
      (node (ref "D58") (pin "C") (pinfunction "C_C") (pintype "passive"))
      (node (ref "R39") (pin "2") (pinfunction "2_2") (pintype "passive"))
      (node (ref "R42") (pin "2") (pinfunction "2_2") (pintype "passive"))
    )
    (net (code "67") (name "Net-(D60-A-PadA1)") (class "Default")
      (node (ref "D60") (pin "A1") (pinfunction "A_A1") (pintype "passive"))
      (node (ref "D60") (pin "A2") (pinfunction "A_A2") (pintype "passive"))
      (node (ref "L9") (pin "2") (pinfunction "2_2") (pintype "passive"))
    )
    (net (code "68") (name "Net-(D60-PadC)") (class "Default")
      (node (ref "D60") (pin "C") (pinfunction "C_C") (pintype "passive"))
      (node (ref "D61") (pin "A1") (pinfunction "A_A1") (pintype "passive"))
      (node (ref "D61") (pin "A2") (pinfunction "A_A2") (pintype "passive"))
    )
    (net (code "69") (name "Net-(D61-PadC)") (class "Default")
      (node (ref "D61") (pin "C") (pinfunction "C_C") (pintype "passive"))
      (node (ref "R43") (pin "2") (pinfunction "2_2") (pintype "passive"))
      (node (ref "R46") (pin "2") (pinfunction "2_2") (pintype "passive"))
    )
    (net (code "70") (name "Net-(D63-A-PadA1)") (class "Default")
      (node (ref "D63") (pin "A1") (pinfunction "A_A1") (pintype "passive"))
      (node (ref "D63") (pin "A2") (pinfunction "A_A2") (pintype "passive"))
      (node (ref "L24") (pin "2") (pinfunction "2_2") (pintype "passive"))
    )
    (net (code "71") (name "Net-(D63-PadC)") (class "Default")
      (node (ref "D63") (pin "C") (pinfunction "C_C") (pintype "passive"))
      (node (ref "D64") (pin "A1") (pinfunction "A_A1") (pintype "passive"))
      (node (ref "D64") (pin "A2") (pinfunction "A_A2") (pintype "passive"))
    )
    (net (code "72") (name "Net-(D64-PadC)") (class "Default")
      (node (ref "D64") (pin "C") (pinfunction "C_C") (pintype "passive"))
      (node (ref "R44") (pin "2") (pinfunction "2_2") (pintype "passive"))
      (node (ref "R47") (pin "2") (pinfunction "2_2") (pintype "passive"))
    )
    (net (code "73") (name "Net-(D66-A-PadA1)") (class "Default")
      (node (ref "D66") (pin "A1") (pinfunction "A_A1") (pintype "passive"))
      (node (ref "D66") (pin "A2") (pinfunction "A_A2") (pintype "passive"))
      (node (ref "L34") (pin "2") (pinfunction "2_2") (pintype "passive"))
    )
    (net (code "74") (name "Net-(D66-PadC)") (class "Default")
      (node (ref "D66") (pin "C") (pinfunction "C_C") (pintype "passive"))
      (node (ref "D67") (pin "A1") (pinfunction "A_A1") (pintype "passive"))
      (node (ref "D67") (pin "A2") (pinfunction "A_A2") (pintype "passive"))
    )
    (net (code "75") (name "Net-(D67-PadC)") (class "Default")
      (node (ref "D67") (pin "C") (pinfunction "C_C") (pintype "passive"))
      (node (ref "R45") (pin "2") (pinfunction "2_2") (pintype "passive"))
      (node (ref "R48") (pin "2") (pinfunction "2_2") (pintype "passive"))
    )
    (net (code "76") (name "Net-(D69-A-PadA1)") (class "Default")
      (node (ref "D69") (pin "A1") (pinfunction "A_A1") (pintype "passive"))
      (node (ref "D69") (pin "A2") (pinfunction "A_A2") (pintype "passive"))
      (node (ref "L10") (pin "2") (pinfunction "2_2") (pintype "passive"))
    )
    (net (code "77") (name "Net-(D69-PadC)") (class "Default")
      (node (ref "D69") (pin "C") (pinfunction "C_C") (pintype "passive"))
      (node (ref "D70") (pin "A1") (pinfunction "A_A1") (pintype "passive"))
      (node (ref "D70") (pin "A2") (pinfunction "A_A2") (pintype "passive"))
    )
    (net (code "78") (name "Net-(D70-PadC)") (class "Default")
      (node (ref "D70") (pin "C") (pinfunction "C_C") (pintype "passive"))
      (node (ref "R52") (pin "2") (pinfunction "2_2") (pintype "passive"))
      (node (ref "R55") (pin "2") (pinfunction "2_2") (pintype "passive"))
    )
    (net (code "79") (name "Net-(D72-A-PadA1)") (class "Default")
      (node (ref "D72") (pin "A1") (pinfunction "A_A1") (pintype "passive"))
      (node (ref "D72") (pin "A2") (pinfunction "A_A2") (pintype "passive"))
      (node (ref "L25") (pin "2") (pinfunction "2_2") (pintype "passive"))
    )
    (net (code "80") (name "Net-(D72-PadC)") (class "Default")
      (node (ref "D72") (pin "C") (pinfunction "C_C") (pintype "passive"))
      (node (ref "D73") (pin "A1") (pinfunction "A_A1") (pintype "passive"))
      (node (ref "D73") (pin "A2") (pinfunction "A_A2") (pintype "passive"))
    )
    (net (code "81") (name "Net-(D73-PadC)") (class "Default")
      (node (ref "D73") (pin "C") (pinfunction "C_C") (pintype "passive"))
      (node (ref "R53") (pin "2") (pinfunction "2_2") (pintype "passive"))
      (node (ref "R56") (pin "2") (pinfunction "2_2") (pintype "passive"))
    )
    (net (code "82") (name "Net-(D75-A-PadA1)") (class "Default")
      (node (ref "D75") (pin "A1") (pinfunction "A_A1") (pintype "passive"))
      (node (ref "D75") (pin "A2") (pinfunction "A_A2") (pintype "passive"))
      (node (ref "L35") (pin "2") (pinfunction "2_2") (pintype "passive"))
    )
    (net (code "83") (name "Net-(D75-PadC)") (class "Default")
      (node (ref "D75") (pin "C") (pinfunction "C_C") (pintype "passive"))
      (node (ref "D76") (pin "A1") (pinfunction "A_A1") (pintype "passive"))
      (node (ref "D76") (pin "A2") (pinfunction "A_A2") (pintype "passive"))
    )
    (net (code "84") (name "Net-(D76-PadC)") (class "Default")
      (node (ref "D76") (pin "C") (pinfunction "C_C") (pintype "passive"))
      (node (ref "R54") (pin "2") (pinfunction "2_2") (pintype "passive"))
      (node (ref "R57") (pin "2") (pinfunction "2_2") (pintype "passive"))
    )
    (net (code "85") (name "Net-(D78-A-PadA1)") (class "Default")
      (node (ref "D78") (pin "A1") (pinfunction "A_A1") (pintype "passive"))
      (node (ref "D78") (pin "A2") (pinfunction "A_A2") (pintype "passive"))
      (node (ref "L11") (pin "2") (pinfunction "2_2") (pintype "passive"))
    )
    (net (code "86") (name "Net-(D78-PadC)") (class "Default")
      (node (ref "D78") (pin "C") (pinfunction "C_C") (pintype "passive"))
      (node (ref "D79") (pin "A1") (pinfunction "A_A1") (pintype "passive"))
      (node (ref "D79") (pin "A2") (pinfunction "A_A2") (pintype "passive"))
    )
    (net (code "87") (name "Net-(D79-PadC)") (class "Default")
      (node (ref "D79") (pin "C") (pinfunction "C_C") (pintype "passive"))
      (node (ref "R58") (pin "2") (pinfunction "2_2") (pintype "passive"))
      (node (ref "R61") (pin "2") (pinfunction "2_2") (pintype "passive"))
    )
    (net (code "88") (name "Net-(D81-A-PadA1)") (class "Default")
      (node (ref "D81") (pin "A1") (pinfunction "A_A1") (pintype "passive"))
      (node (ref "D81") (pin "A2") (pinfunction "A_A2") (pintype "passive"))
      (node (ref "L26") (pin "2") (pinfunction "2_2") (pintype "passive"))
    )
    (net (code "89") (name "Net-(D81-PadC)") (class "Default")
      (node (ref "D81") (pin "C") (pinfunction "C_C") (pintype "passive"))
      (node (ref "D82") (pin "A1") (pinfunction "A_A1") (pintype "passive"))
      (node (ref "D82") (pin "A2") (pinfunction "A_A2") (pintype "passive"))
    )
    (net (code "90") (name "Net-(D82-PadC)") (class "Default")
      (node (ref "D82") (pin "C") (pinfunction "C_C") (pintype "passive"))
      (node (ref "R59") (pin "2") (pinfunction "2_2") (pintype "passive"))
      (node (ref "R62") (pin "2") (pinfunction "2_2") (pintype "passive"))
    )
    (net (code "91") (name "Net-(D84-A-PadA1)") (class "Default")
      (node (ref "D84") (pin "A1") (pinfunction "A_A1") (pintype "passive"))
      (node (ref "D84") (pin "A2") (pinfunction "A_A2") (pintype "passive"))
      (node (ref "L36") (pin "2") (pinfunction "2_2") (pintype "passive"))
    )
    (net (code "92") (name "Net-(D84-PadC)") (class "Default")
      (node (ref "D84") (pin "C") (pinfunction "C_C") (pintype "passive"))
      (node (ref "D85") (pin "A1") (pinfunction "A_A1") (pintype "passive"))
      (node (ref "D85") (pin "A2") (pinfunction "A_A2") (pintype "passive"))
    )
    (net (code "93") (name "Net-(D85-PadC)") (class "Default")
      (node (ref "D85") (pin "C") (pinfunction "C_C") (pintype "passive"))
      (node (ref "R60") (pin "2") (pinfunction "2_2") (pintype "passive"))
      (node (ref "R63") (pin "2") (pinfunction "2_2") (pintype "passive"))
    )
    (net (code "94") (name "Net-(D87-A-PadA1)") (class "Default")
      (node (ref "D87") (pin "A1") (pinfunction "A_A1") (pintype "passive"))
      (node (ref "D87") (pin "A2") (pinfunction "A_A2") (pintype "passive"))
      (node (ref "L12") (pin "2") (pinfunction "2_2") (pintype "passive"))
    )
    (net (code "95") (name "Net-(D87-PadC)") (class "Default")
      (node (ref "D87") (pin "C") (pinfunction "C_C") (pintype "passive"))
      (node (ref "D88") (pin "A1") (pinfunction "A_A1") (pintype "passive"))
      (node (ref "D88") (pin "A2") (pinfunction "A_A2") (pintype "passive"))
    )
    (net (code "96") (name "Net-(D88-PadC)") (class "Default")
      (node (ref "D88") (pin "C") (pinfunction "C_C") (pintype "passive"))
      (node (ref "R64") (pin "2") (pinfunction "2_2") (pintype "passive"))
      (node (ref "R67") (pin "2") (pinfunction "2_2") (pintype "passive"))
    )
    (net (code "97") (name "Net-(D90-A-PadA1)") (class "Default")
      (node (ref "D90") (pin "A1") (pinfunction "A_A1") (pintype "passive"))
      (node (ref "D90") (pin "A2") (pinfunction "A_A2") (pintype "passive"))
      (node (ref "L27") (pin "2") (pinfunction "2_2") (pintype "passive"))
    )
    (net (code "98") (name "Net-(D90-PadC)") (class "Default")
      (node (ref "D90") (pin "C") (pinfunction "C_C") (pintype "passive"))
      (node (ref "D91") (pin "A1") (pinfunction "A_A1") (pintype "passive"))
      (node (ref "D91") (pin "A2") (pinfunction "A_A2") (pintype "passive"))
    )
    (net (code "99") (name "Net-(D91-PadC)") (class "Default")
      (node (ref "D91") (pin "C") (pinfunction "C_C") (pintype "passive"))
      (node (ref "R65") (pin "2") (pinfunction "2_2") (pintype "passive"))
      (node (ref "R68") (pin "2") (pinfunction "2_2") (pintype "passive"))
    )
    (net (code "100") (name "Net-(D93-A-PadA1)") (class "Default")
      (node (ref "D93") (pin "A1") (pinfunction "A_A1") (pintype "passive"))
      (node (ref "D93") (pin "A2") (pinfunction "A_A2") (pintype "passive"))
      (node (ref "L37") (pin "2") (pinfunction "2_2") (pintype "passive"))
    )
    (net (code "101") (name "Net-(D93-PadC)") (class "Default")
      (node (ref "D93") (pin "C") (pinfunction "C_C") (pintype "passive"))
      (node (ref "D94") (pin "A1") (pinfunction "A_A1") (pintype "passive"))
      (node (ref "D94") (pin "A2") (pinfunction "A_A2") (pintype "passive"))
    )
    (net (code "102") (name "Net-(D94-PadC)") (class "Default")
      (node (ref "D94") (pin "C") (pinfunction "C_C") (pintype "passive"))
      (node (ref "R66") (pin "2") (pinfunction "2_2") (pintype "passive"))
      (node (ref "R69") (pin "2") (pinfunction "2_2") (pintype "passive"))
    )
    (net (code "103") (name "Net-(D96-A-PadA1)") (class "Default")
      (node (ref "D96") (pin "A1") (pinfunction "A_A1") (pintype "passive"))
      (node (ref "D96") (pin "A2") (pinfunction "A_A2") (pintype "passive"))
      (node (ref "L13") (pin "2") (pinfunction "2_2") (pintype "passive"))
    )
    (net (code "104") (name "Net-(D96-PadC)") (class "Default")
      (node (ref "D96") (pin "C") (pinfunction "C_C") (pintype "passive"))
      (node (ref "D97") (pin "A1") (pinfunction "A_A1") (pintype "passive"))
      (node (ref "D97") (pin "A2") (pinfunction "A_A2") (pintype "passive"))
    )
    (net (code "105") (name "Net-(D97-PadC)") (class "Default")
      (node (ref "D97") (pin "C") (pinfunction "C_C") (pintype "passive"))
      (node (ref "R70") (pin "2") (pinfunction "2_2") (pintype "passive"))
      (node (ref "R73") (pin "2") (pinfunction "2_2") (pintype "passive"))
    )
    (net (code "106") (name "Net-(D99-A-PadA1)") (class "Default")
      (node (ref "D99") (pin "A1") (pinfunction "A_A1") (pintype "passive"))
      (node (ref "D99") (pin "A2") (pinfunction "A_A2") (pintype "passive"))
      (node (ref "L28") (pin "2") (pinfunction "2_2") (pintype "passive"))
    )
    (net (code "107") (name "Net-(D100-A-PadA1)") (class "Default")
      (node (ref "D100") (pin "A1") (pinfunction "A_A1") (pintype "passive"))
      (node (ref "D100") (pin "A2") (pinfunction "A_A2") (pintype "passive"))
      (node (ref "D99") (pin "C") (pinfunction "C_C") (pintype "passive"))
    )
    (net (code "108") (name "Net-(D100-PadC)") (class "Default")
      (node (ref "D100") (pin "C") (pinfunction "C_C") (pintype "passive"))
      (node (ref "R71") (pin "2") (pinfunction "2_2") (pintype "passive"))
      (node (ref "R74") (pin "2") (pinfunction "2_2") (pintype "passive"))
    )
    (net (code "109") (name "Net-(D102-A-PadA1)") (class "Default")
      (node (ref "D102") (pin "A1") (pinfunction "A_A1") (pintype "passive"))
      (node (ref "D102") (pin "A2") (pinfunction "A_A2") (pintype "passive"))
      (node (ref "L38") (pin "2") (pinfunction "2_2") (pintype "passive"))
    )
    (net (code "110") (name "Net-(D102-PadC)") (class "Default")
      (node (ref "D102") (pin "C") (pinfunction "C_C") (pintype "passive"))
      (node (ref "D103") (pin "A1") (pinfunction "A_A1") (pintype "passive"))
      (node (ref "D103") (pin "A2") (pinfunction "A_A2") (pintype "passive"))
    )
    (net (code "111") (name "Net-(D103-PadC)") (class "Default")
      (node (ref "D103") (pin "C") (pinfunction "C_C") (pintype "passive"))
      (node (ref "R72") (pin "2") (pinfunction "2_2") (pintype "passive"))
      (node (ref "R75") (pin "2") (pinfunction "2_2") (pintype "passive"))
    )
    (net (code "112") (name "Net-(D105-A-PadA1)") (class "Default")
      (node (ref "D105") (pin "A1") (pinfunction "A_A1") (pintype "passive"))
      (node (ref "D105") (pin "A2") (pinfunction "A_A2") (pintype "passive"))
      (node (ref "L14") (pin "2") (pinfunction "2_2") (pintype "passive"))
    )
    (net (code "113") (name "Net-(D105-PadC)") (class "Default")
      (node (ref "D105") (pin "C") (pinfunction "C_C") (pintype "passive"))
      (node (ref "D106") (pin "A1") (pinfunction "A_A1") (pintype "passive"))
      (node (ref "D106") (pin "A2") (pinfunction "A_A2") (pintype "passive"))
    )
    (net (code "114") (name "Net-(D106-PadC)") (class "Default")
      (node (ref "D106") (pin "C") (pinfunction "C_C") (pintype "passive"))
      (node (ref "R76") (pin "2") (pinfunction "2_2") (pintype "passive"))
      (node (ref "R79") (pin "2") (pinfunction "2_2") (pintype "passive"))
    )
    (net (code "115") (name "Net-(D108-A-PadA1)") (class "Default")
      (node (ref "D108") (pin "A1") (pinfunction "A_A1") (pintype "passive"))
      (node (ref "D108") (pin "A2") (pinfunction "A_A2") (pintype "passive"))
      (node (ref "L29") (pin "2") (pinfunction "2_2") (pintype "passive"))
    )
    (net (code "116") (name "Net-(D108-PadC)") (class "Default")
      (node (ref "D108") (pin "C") (pinfunction "C_C") (pintype "passive"))
      (node (ref "D109") (pin "A1") (pinfunction "A_A1") (pintype "passive"))
      (node (ref "D109") (pin "A2") (pinfunction "A_A2") (pintype "passive"))
    )
    (net (code "117") (name "Net-(D109-PadC)") (class "Default")
      (node (ref "D109") (pin "C") (pinfunction "C_C") (pintype "passive"))
      (node (ref "R77") (pin "2") (pinfunction "2_2") (pintype "passive"))
      (node (ref "R80") (pin "2") (pinfunction "2_2") (pintype "passive"))
    )
    (net (code "118") (name "Net-(D111-A-PadA1)") (class "Default")
      (node (ref "D111") (pin "A1") (pinfunction "A_A1") (pintype "passive"))
      (node (ref "D111") (pin "A2") (pinfunction "A_A2") (pintype "passive"))
      (node (ref "L39") (pin "2") (pinfunction "2_2") (pintype "passive"))
    )
    (net (code "119") (name "Net-(D111-PadC)") (class "Default")
      (node (ref "D111") (pin "C") (pinfunction "C_C") (pintype "passive"))
      (node (ref "D112") (pin "A1") (pinfunction "A_A1") (pintype "passive"))
      (node (ref "D112") (pin "A2") (pinfunction "A_A2") (pintype "passive"))
    )
    (net (code "120") (name "Net-(D112-PadC)") (class "Default")
      (node (ref "D112") (pin "C") (pinfunction "C_C") (pintype "passive"))
      (node (ref "R78") (pin "2") (pinfunction "2_2") (pintype "passive"))
      (node (ref "R81") (pin "2") (pinfunction "2_2") (pintype "passive"))
    )
    (net (code "121") (name "Net-(D114-A-PadA1)") (class "Default")
      (node (ref "D114") (pin "A1") (pinfunction "A_A1") (pintype "passive"))
      (node (ref "D114") (pin "A2") (pinfunction "A_A2") (pintype "passive"))
      (node (ref "L15") (pin "2") (pinfunction "2_2") (pintype "passive"))
    )
    (net (code "122") (name "Net-(D114-PadC)") (class "Default")
      (node (ref "D114") (pin "C") (pinfunction "C_C") (pintype "passive"))
      (node (ref "D115") (pin "A1") (pinfunction "A_A1") (pintype "passive"))
      (node (ref "D115") (pin "A2") (pinfunction "A_A2") (pintype "passive"))
    )
    (net (code "123") (name "Net-(D115-PadC)") (class "Default")
      (node (ref "D115") (pin "C") (pinfunction "C_C") (pintype "passive"))
      (node (ref "R85") (pin "2") (pinfunction "2_2") (pintype "passive"))
      (node (ref "R88") (pin "2") (pinfunction "2_2") (pintype "passive"))
    )
    (net (code "124") (name "Net-(D117-A-PadA1)") (class "Default")
      (node (ref "D117") (pin "A1") (pinfunction "A_A1") (pintype "passive"))
      (node (ref "D117") (pin "A2") (pinfunction "A_A2") (pintype "passive"))
      (node (ref "L30") (pin "2") (pinfunction "2_2") (pintype "passive"))
    )
    (net (code "125") (name "Net-(D117-PadC)") (class "Default")
      (node (ref "D117") (pin "C") (pinfunction "C_C") (pintype "passive"))
      (node (ref "D118") (pin "A1") (pinfunction "A_A1") (pintype "passive"))
      (node (ref "D118") (pin "A2") (pinfunction "A_A2") (pintype "passive"))
    )
    (net (code "126") (name "Net-(D118-PadC)") (class "Default")
      (node (ref "D118") (pin "C") (pinfunction "C_C") (pintype "passive"))
      (node (ref "R86") (pin "2") (pinfunction "2_2") (pintype "passive"))
      (node (ref "R89") (pin "2") (pinfunction "2_2") (pintype "passive"))
    )
    (net (code "127") (name "Net-(D120-A-PadA1)") (class "Default")
      (node (ref "D120") (pin "A1") (pinfunction "A_A1") (pintype "passive"))
      (node (ref "D120") (pin "A2") (pinfunction "A_A2") (pintype "passive"))
      (node (ref "L40") (pin "2") (pinfunction "2_2") (pintype "passive"))
    )
    (net (code "128") (name "Net-(D120-PadC)") (class "Default")
      (node (ref "D120") (pin "C") (pinfunction "C_C") (pintype "passive"))
      (node (ref "D121") (pin "A1") (pinfunction "A_A1") (pintype "passive"))
      (node (ref "D121") (pin "A2") (pinfunction "A_A2") (pintype "passive"))
    )
    (net (code "129") (name "Net-(D121-PadC)") (class "Default")
      (node (ref "D121") (pin "C") (pinfunction "C_C") (pintype "passive"))
      (node (ref "R87") (pin "2") (pinfunction "2_2") (pintype "passive"))
      (node (ref "R90") (pin "2") (pinfunction "2_2") (pintype "passive"))
    )
    (net (code "130") (name "Net-(Q1-D-Pad5)") (class "Default")
      (node (ref "Q1") (pin "5") (pinfunction "D_5") (pintype "bidirectional"))
      (node (ref "Q1") (pin "6") (pinfunction "D_6") (pintype "bidirectional"))
      (node (ref "Q1") (pin "7") (pinfunction "D_7") (pintype "bidirectional"))
      (node (ref "Q1") (pin "8") (pinfunction "D_8") (pintype "bidirectional"))
      (node (ref "R1") (pin "1") (pinfunction "1_1") (pintype "passive"))
      (node (ref "R11") (pin "1") (pinfunction "1_1") (pintype "passive"))
      (node (ref "R13") (pin "1") (pinfunction "1_1") (pintype "passive"))
      (node (ref "R15") (pin "1") (pinfunction "1_1") (pintype "passive"))
      (node (ref "R17") (pin "1") (pinfunction "1_1") (pintype "passive"))
      (node (ref "R21") (pin "1") (pinfunction "1_1") (pintype "passive"))
      (node (ref "R23") (pin "1") (pinfunction "1_1") (pintype "passive"))
      (node (ref "R3") (pin "1") (pinfunction "1_1") (pintype "passive"))
      (node (ref "R6") (pin "1") (pinfunction "1_1") (pintype "passive"))
      (node (ref "R8") (pin "1") (pinfunction "1_1") (pintype "passive"))
    )
    (net (code "131") (name "Net-(Q1-G)") (class "Default")
      (node (ref "Q1") (pin "4") (pinfunction "G_4") (pintype "bidirectional"))
      (node (ref "R19") (pin "2") (pinfunction "2_2") (pintype "passive"))
    )
    (net (code "132") (name "Net-(Q2-D-Pad5)") (class "Default")
      (node (ref "Q2") (pin "5") (pinfunction "D_5") (pintype "bidirectional"))
      (node (ref "Q2") (pin "6") (pinfunction "D_6") (pintype "bidirectional"))
      (node (ref "Q2") (pin "7") (pinfunction "D_7") (pintype "bidirectional"))
      (node (ref "Q2") (pin "8") (pinfunction "D_8") (pintype "bidirectional"))
      (node (ref "R12") (pin "1") (pinfunction "1_1") (pintype "passive"))
      (node (ref "R14") (pin "1") (pinfunction "1_1") (pintype "passive"))
      (node (ref "R16") (pin "1") (pinfunction "1_1") (pintype "passive"))
      (node (ref "R18") (pin "1") (pinfunction "1_1") (pintype "passive"))
      (node (ref "R2") (pin "1") (pinfunction "1_1") (pintype "passive"))
      (node (ref "R22") (pin "1") (pinfunction "1_1") (pintype "passive"))
      (node (ref "R24") (pin "1") (pinfunction "1_1") (pintype "passive"))
      (node (ref "R4") (pin "1") (pinfunction "1_1") (pintype "passive"))
      (node (ref "R7") (pin "1") (pinfunction "1_1") (pintype "passive"))
      (node (ref "R9") (pin "1") (pinfunction "1_1") (pintype "passive"))
    )
    (net (code "133") (name "Net-(Q2-G)") (class "Default")
      (node (ref "Q2") (pin "4") (pinfunction "G_4") (pintype "bidirectional"))
      (node (ref "R20") (pin "2") (pinfunction "2_2") (pintype "passive"))
    )
    (net (code "134") (name "Net-(Q3-D-Pad5)") (class "Default")
      (node (ref "Q3") (pin "5") (pinfunction "D_5") (pintype "bidirectional"))
      (node (ref "Q3") (pin "6") (pinfunction "D_6") (pintype "bidirectional"))
      (node (ref "Q3") (pin "7") (pinfunction "D_7") (pintype "bidirectional"))
      (node (ref "Q3") (pin "8") (pinfunction "D_8") (pintype "bidirectional"))
      (node (ref "Q3") (pin "PAD") (pinfunction "D_PAD") (pintype "bidirectional"))
      (node (ref "TP1") (pin "TP") (pinfunction "TP_TP") (pintype "bidirectional"))
    )
    (net (code "135") (name "Net-(Q3-G)") (class "Default")
      (node (ref "Q3") (pin "4") (pinfunction "G_4") (pintype "bidirectional"))
      (node (ref "U4") (pin "7") (pinfunction "OUT_7") (pintype "output"))
    )
    (net (code "136") (name "Net-(Q4-D-Pad5)") (class "Default")
      (node (ref "Q4") (pin "5") (pinfunction "D_5") (pintype "bidirectional"))
      (node (ref "Q4") (pin "6") (pinfunction "D_6") (pintype "bidirectional"))
      (node (ref "Q4") (pin "7") (pinfunction "D_7") (pintype "bidirectional"))
      (node (ref "Q4") (pin "8") (pinfunction "D_8") (pintype "bidirectional"))
      (node (ref "R25") (pin "1") (pinfunction "1_1") (pintype "passive"))
      (node (ref "R28") (pin "1") (pinfunction "1_1") (pintype "passive"))
      (node (ref "R31") (pin "1") (pinfunction "1_1") (pintype "passive"))
      (node (ref "R34") (pin "1") (pinfunction "1_1") (pintype "passive"))
      (node (ref "R37") (pin "1") (pinfunction "1_1") (pintype "passive"))
      (node (ref "R40") (pin "1") (pinfunction "1_1") (pintype "passive"))
      (node (ref "R43") (pin "1") (pinfunction "1_1") (pintype "passive"))
      (node (ref "R46") (pin "1") (pinfunction "1_1") (pintype "passive"))
      (node (ref "R52") (pin "1") (pinfunction "1_1") (pintype "passive"))
      (node (ref "R55") (pin "1") (pinfunction "1_1") (pintype "passive"))
    )
    (net (code "137") (name "Net-(Q4-G)") (class "Default")
      (node (ref "Q4") (pin "4") (pinfunction "G_4") (pintype "bidirectional"))
      (node (ref "R50") (pin "2") (pinfunction "2_2") (pintype "passive"))
    )
    (net (code "138") (name "Net-(Q5-D-Pad5)") (class "Default")
      (node (ref "Q5") (pin "5") (pinfunction "D_5") (pintype "bidirectional"))
      (node (ref "Q5") (pin "6") (pinfunction "D_6") (pintype "bidirectional"))
      (node (ref "Q5") (pin "7") (pinfunction "D_7") (pintype "bidirectional"))
      (node (ref "Q5") (pin "8") (pinfunction "D_8") (pintype "bidirectional"))
      (node (ref "R26") (pin "1") (pinfunction "1_1") (pintype "passive"))
      (node (ref "R29") (pin "1") (pinfunction "1_1") (pintype "passive"))
      (node (ref "R32") (pin "1") (pinfunction "1_1") (pintype "passive"))
      (node (ref "R35") (pin "1") (pinfunction "1_1") (pintype "passive"))
      (node (ref "R38") (pin "1") (pinfunction "1_1") (pintype "passive"))
      (node (ref "R41") (pin "1") (pinfunction "1_1") (pintype "passive"))
      (node (ref "R44") (pin "1") (pinfunction "1_1") (pintype "passive"))
      (node (ref "R47") (pin "1") (pinfunction "1_1") (pintype "passive"))
      (node (ref "R53") (pin "1") (pinfunction "1_1") (pintype "passive"))
      (node (ref "R56") (pin "1") (pinfunction "1_1") (pintype "passive"))
    )
    (net (code "139") (name "Net-(Q5-G)") (class "Default")
      (node (ref "Q5") (pin "4") (pinfunction "G_4") (pintype "bidirectional"))
      (node (ref "R51") (pin "2") (pinfunction "2_2") (pintype "passive"))
    )
    (net (code "140") (name "Net-(Q6-D-Pad5)") (class "Default")
      (node (ref "Q6") (pin "5") (pinfunction "D_5") (pintype "bidirectional"))
      (node (ref "Q6") (pin "6") (pinfunction "D_6") (pintype "bidirectional"))
      (node (ref "Q6") (pin "7") (pinfunction "D_7") (pintype "bidirectional"))
      (node (ref "Q6") (pin "8") (pinfunction "D_8") (pintype "bidirectional"))
      (node (ref "R27") (pin "1") (pinfunction "1_1") (pintype "passive"))
      (node (ref "R30") (pin "1") (pinfunction "1_1") (pintype "passive"))
      (node (ref "R33") (pin "1") (pinfunction "1_1") (pintype "passive"))
      (node (ref "R36") (pin "1") (pinfunction "1_1") (pintype "passive"))
      (node (ref "R39") (pin "1") (pinfunction "1_1") (pintype "passive"))
      (node (ref "R42") (pin "1") (pinfunction "1_1") (pintype "passive"))
      (node (ref "R45") (pin "1") (pinfunction "1_1") (pintype "passive"))
      (node (ref "R48") (pin "1") (pinfunction "1_1") (pintype "passive"))
      (node (ref "R54") (pin "1") (pinfunction "1_1") (pintype "passive"))
      (node (ref "R57") (pin "1") (pinfunction "1_1") (pintype "passive"))
    )
    (net (code "141") (name "Net-(Q6-G)") (class "Default")
      (node (ref "Q6") (pin "4") (pinfunction "G_4") (pintype "bidirectional"))
      (node (ref "R49") (pin "2") (pinfunction "2_2") (pintype "passive"))
    )
    (net (code "142") (name "Net-(Q7-D-Pad5)") (class "Default")
      (node (ref "Q7") (pin "5") (pinfunction "D_5") (pintype "bidirectional"))
      (node (ref "Q7") (pin "6") (pinfunction "D_6") (pintype "bidirectional"))
      (node (ref "Q7") (pin "7") (pinfunction "D_7") (pintype "bidirectional"))
      (node (ref "Q7") (pin "8") (pinfunction "D_8") (pintype "bidirectional"))
      (node (ref "R58") (pin "1") (pinfunction "1_1") (pintype "passive"))
      (node (ref "R61") (pin "1") (pinfunction "1_1") (pintype "passive"))
      (node (ref "R64") (pin "1") (pinfunction "1_1") (pintype "passive"))
      (node (ref "R67") (pin "1") (pinfunction "1_1") (pintype "passive"))
      (node (ref "R70") (pin "1") (pinfunction "1_1") (pintype "passive"))
      (node (ref "R73") (pin "1") (pinfunction "1_1") (pintype "passive"))
      (node (ref "R76") (pin "1") (pinfunction "1_1") (pintype "passive"))
      (node (ref "R79") (pin "1") (pinfunction "1_1") (pintype "passive"))
      (node (ref "R85") (pin "1") (pinfunction "1_1") (pintype "passive"))
      (node (ref "R88") (pin "1") (pinfunction "1_1") (pintype "passive"))
    )
    (net (code "143") (name "Net-(Q7-G)") (class "Default")
      (node (ref "Q7") (pin "4") (pinfunction "G_4") (pintype "bidirectional"))
      (node (ref "R82") (pin "2") (pinfunction "2_2") (pintype "passive"))
    )
    (net (code "144") (name "Net-(Q8-D-Pad5)") (class "Default")
      (node (ref "Q8") (pin "5") (pinfunction "D_5") (pintype "bidirectional"))
      (node (ref "Q8") (pin "6") (pinfunction "D_6") (pintype "bidirectional"))
      (node (ref "Q8") (pin "7") (pinfunction "D_7") (pintype "bidirectional"))
      (node (ref "Q8") (pin "8") (pinfunction "D_8") (pintype "bidirectional"))
      (node (ref "R59") (pin "1") (pinfunction "1_1") (pintype "passive"))
      (node (ref "R62") (pin "1") (pinfunction "1_1") (pintype "passive"))
      (node (ref "R65") (pin "1") (pinfunction "1_1") (pintype "passive"))
      (node (ref "R68") (pin "1") (pinfunction "1_1") (pintype "passive"))
      (node (ref "R71") (pin "1") (pinfunction "1_1") (pintype "passive"))
      (node (ref "R74") (pin "1") (pinfunction "1_1") (pintype "passive"))
      (node (ref "R77") (pin "1") (pinfunction "1_1") (pintype "passive"))
      (node (ref "R80") (pin "1") (pinfunction "1_1") (pintype "passive"))
      (node (ref "R86") (pin "1") (pinfunction "1_1") (pintype "passive"))
      (node (ref "R89") (pin "1") (pinfunction "1_1") (pintype "passive"))
    )
    (net (code "145") (name "Net-(Q8-G)") (class "Default")
      (node (ref "Q8") (pin "4") (pinfunction "G_4") (pintype "bidirectional"))
      (node (ref "R83") (pin "2") (pinfunction "2_2") (pintype "passive"))
    )
    (net (code "146") (name "Net-(Q9-D-Pad5)") (class "Default")
      (node (ref "Q9") (pin "5") (pinfunction "D_5") (pintype "bidirectional"))
      (node (ref "Q9") (pin "6") (pinfunction "D_6") (pintype "bidirectional"))
      (node (ref "Q9") (pin "7") (pinfunction "D_7") (pintype "bidirectional"))
      (node (ref "Q9") (pin "8") (pinfunction "D_8") (pintype "bidirectional"))
      (node (ref "R60") (pin "1") (pinfunction "1_1") (pintype "passive"))
      (node (ref "R63") (pin "1") (pinfunction "1_1") (pintype "passive"))
      (node (ref "R66") (pin "1") (pinfunction "1_1") (pintype "passive"))
      (node (ref "R69") (pin "1") (pinfunction "1_1") (pintype "passive"))
      (node (ref "R72") (pin "1") (pinfunction "1_1") (pintype "passive"))
      (node (ref "R75") (pin "1") (pinfunction "1_1") (pintype "passive"))
      (node (ref "R78") (pin "1") (pinfunction "1_1") (pintype "passive"))
      (node (ref "R81") (pin "1") (pinfunction "1_1") (pintype "passive"))
      (node (ref "R87") (pin "1") (pinfunction "1_1") (pintype "passive"))
      (node (ref "R90") (pin "1") (pinfunction "1_1") (pintype "passive"))
    )
    (net (code "147") (name "Net-(Q9-G)") (class "Default")
      (node (ref "Q9") (pin "4") (pinfunction "G_4") (pintype "bidirectional"))
      (node (ref "R84") (pin "2") (pinfunction "2_2") (pintype "passive"))
    )
    (net (code "148") (name "Net-(U1-OUT)") (class "Default")
      (node (ref "R19") (pin "1") (pinfunction "1_1") (pintype "passive"))
      (node (ref "U1") (pin "5") (pinfunction "OUT_5") (pintype "output"))
    )
    (net (code "149") (name "Net-(U2-OUT)") (class "Default")
      (node (ref "R20") (pin "1") (pinfunction "1_1") (pintype "passive"))
      (node (ref "U2") (pin "5") (pinfunction "OUT_5") (pintype "output"))
    )
    (net (code "150") (name "Net-(U3-C)") (class "Default")
      (node (ref "C15") (pin "2") (pinfunction "2_2") (pintype "passive"))
      (node (ref "U3") (pin "C2") (pinfunction "C_C2") (pintype "input"))
    )
    (net (code "151") (name "Net-(U3-Q)") (class "Default")
      (node (ref "U3") (pin "D2") (pinfunction "Q_D2") (pintype "output"))
      (node (ref "U4") (pin "1") (pinfunction "IN_1") (pintype "input"))
    )
    (net (code "152") (name "Net-(U3-R{slash}C)") (class "Default")
      (node (ref "C15") (pin "1") (pinfunction "1_1") (pintype "passive"))
      (node (ref "R10") (pin "2") (pinfunction "2_2") (pintype "passive"))
      (node (ref "U3") (pin "B2") (pinfunction "R/C_B2") (pintype "input"))
    )
    (net (code "153") (name "Net-(U4-PHA)") (class "Default")
      (node (ref "C10") (pin "1") (pinfunction "1_1") (pintype "passive"))
      (node (ref "C5") (pin "1") (pinfunction "1_1") (pintype "passive"))
      (node (ref "J1") (pin "10") (pinfunction "10_10") (pintype "bidirectional"))
      (node (ref "J1") (pin "11") (pinfunction "11_11") (pintype "bidirectional"))
      (node (ref "J1") (pin "2") (pinfunction "2_2") (pintype "bidirectional"))
      (node (ref "J1") (pin "3") (pinfunction "3_3") (pintype "bidirectional"))
      (node (ref "J1") (pin "4") (pinfunction "4_4") (pintype "bidirectional"))
      (node (ref "J1") (pin "5") (pinfunction "5_5") (pintype "bidirectional"))
      (node (ref "J1") (pin "6") (pinfunction "6_6") (pintype "bidirectional"))
      (node (ref "J1") (pin "7") (pinfunction "7_7") (pintype "bidirectional"))
      (node (ref "J1") (pin "8") (pinfunction "8_8") (pintype "bidirectional"))
      (node (ref "J1") (pin "9") (pinfunction "9_9") (pintype "bidirectional"))
      (node (ref "Q3") (pin "1") (pinfunction "S_1") (pintype "bidirectional"))
      (node (ref "Q3") (pin "2") (pinfunction "S_2") (pintype "bidirectional"))
      (node (ref "Q3") (pin "3") (pinfunction "S_3") (pintype "bidirectional"))
      (node (ref "U4") (pin "3") (pinfunction "PHA_3") (pintype "input"))
      (node (ref "U4") (pin "8") (pinfunction "VCC_8") (pintype "power_in"))
    )
    (net (code "154") (name "Net-(U6-OUT)") (class "Default")
      (node (ref "R51") (pin "1") (pinfunction "1_1") (pintype "passive"))
      (node (ref "U6") (pin "5") (pinfunction "OUT_5") (pintype "output"))
    )
    (net (code "155") (name "Net-(U7-OUT)") (class "Default")
      (node (ref "R49") (pin "1") (pinfunction "1_1") (pintype "passive"))
      (node (ref "U7") (pin "5") (pinfunction "OUT_5") (pintype "output"))
    )
    (net (code "156") (name "Net-(U8-OUT)") (class "Default")
      (node (ref "R82") (pin "1") (pinfunction "1_1") (pintype "passive"))
      (node (ref "U8") (pin "5") (pinfunction "OUT_5") (pintype "output"))
    )
    (net (code "157") (name "Net-(U9-OUT)") (class "Default")
      (node (ref "R83") (pin "1") (pinfunction "1_1") (pintype "passive"))
      (node (ref "U9") (pin "5") (pinfunction "OUT_5") (pintype "output"))
    )
    (net (code "158") (name "Net-(U10-OUT)") (class "Default")
      (node (ref "R84") (pin "1") (pinfunction "1_1") (pintype "passive"))
      (node (ref "U10") (pin "5") (pinfunction "OUT_5") (pintype "output"))
    )
    (net (code "159") (name "RED_C") (class "Default")
      (node (ref "D31") (pin "1") (pinfunction "CR_1") (pintype "passive"))
      (node (ref "J1") (pin "22") (pinfunction "22_22") (pintype "bidirectional"))
    )
    (net (code "160") (name "SYNC") (class "Default")
      (node (ref "J1") (pin "20") (pinfunction "20_20") (pintype "bidirectional"))
      (node (ref "R5") (pin "2") (pinfunction "2_2") (pintype "passive"))
      (node (ref "U1") (pin "3") (pinfunction "IN+_3") (pintype "input"))
      (node (ref "U10") (pin "3") (pinfunction "IN+_3") (pintype "input"))
      (node (ref "U2") (pin "3") (pinfunction "IN+_3") (pintype "input"))
      (node (ref "U5") (pin "3") (pinfunction "IN+_3") (pintype "input"))
      (node (ref "U6") (pin "3") (pinfunction "IN+_3") (pintype "input"))
      (node (ref "U7") (pin "3") (pinfunction "IN+_3") (pintype "input"))
      (node (ref "U8") (pin "3") (pinfunction "IN+_3") (pintype "input"))
      (node (ref "U9") (pin "3") (pinfunction "IN+_3") (pintype "input"))
    )
    (net (code "161") (name "WHITE_C") (class "Default")
      (node (ref "J1") (pin "16") (pinfunction "16_16") (pintype "bidirectional"))
    )
  )
)
